# io-board-d-7.net
KiCad netlist of a schematic drawn in EAGLE
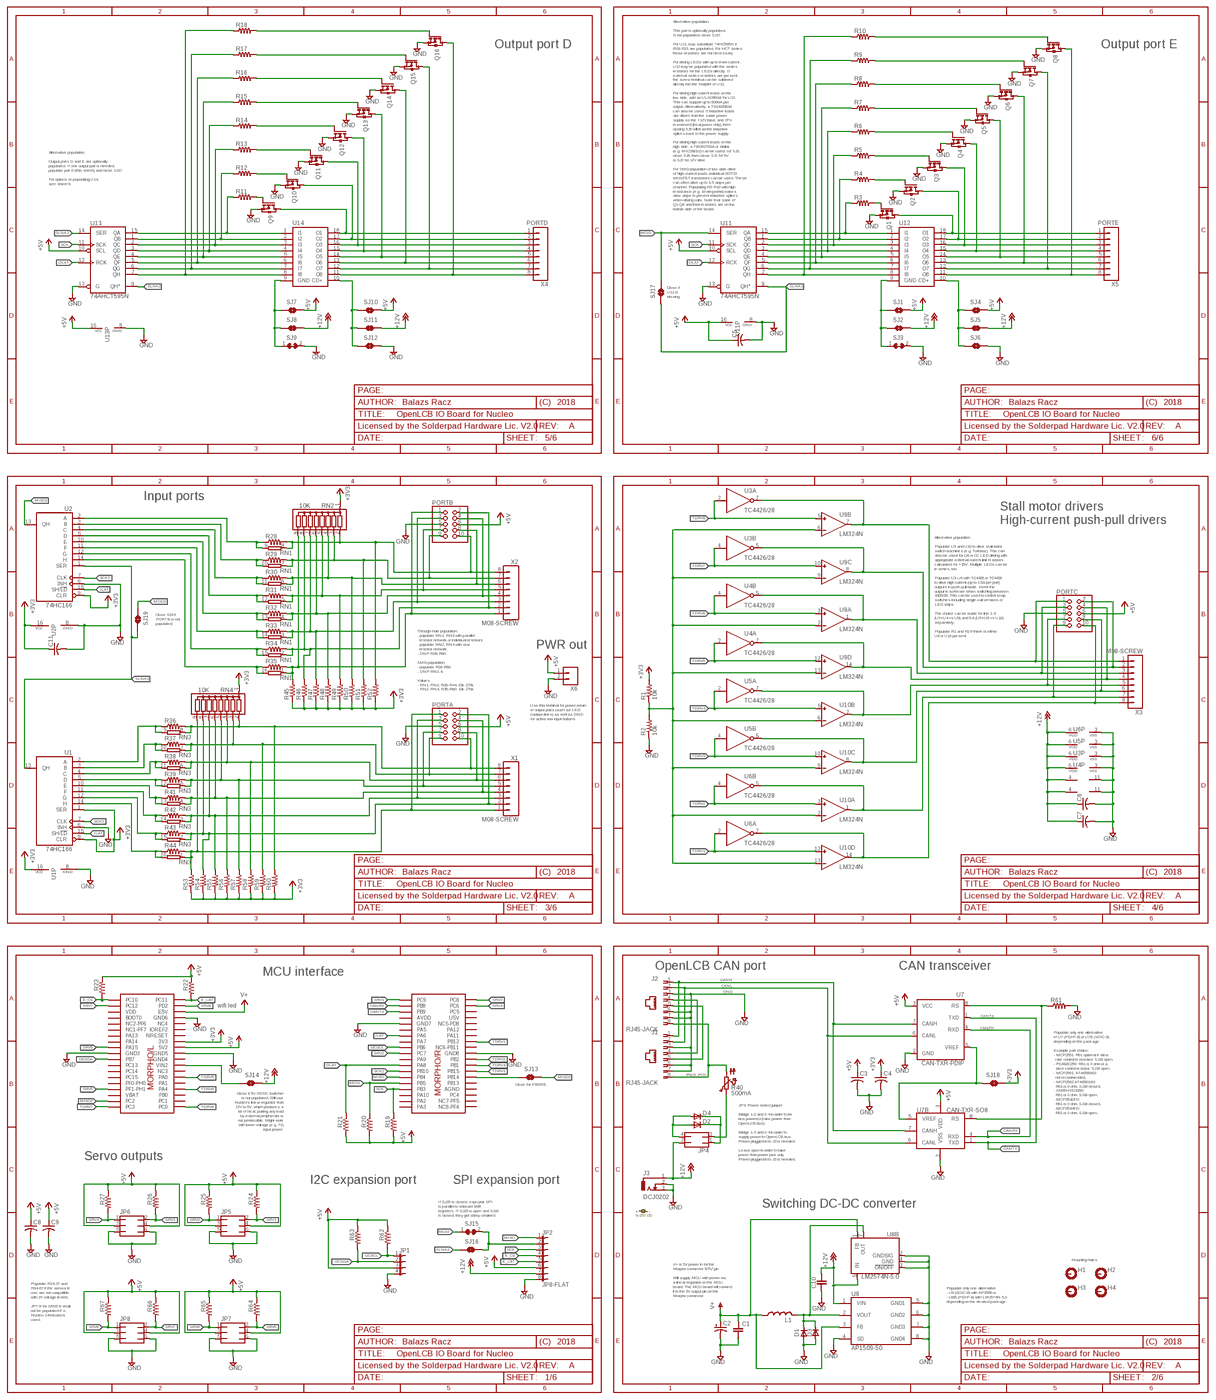
[diagram p0: schematic, sheet 1, overview]
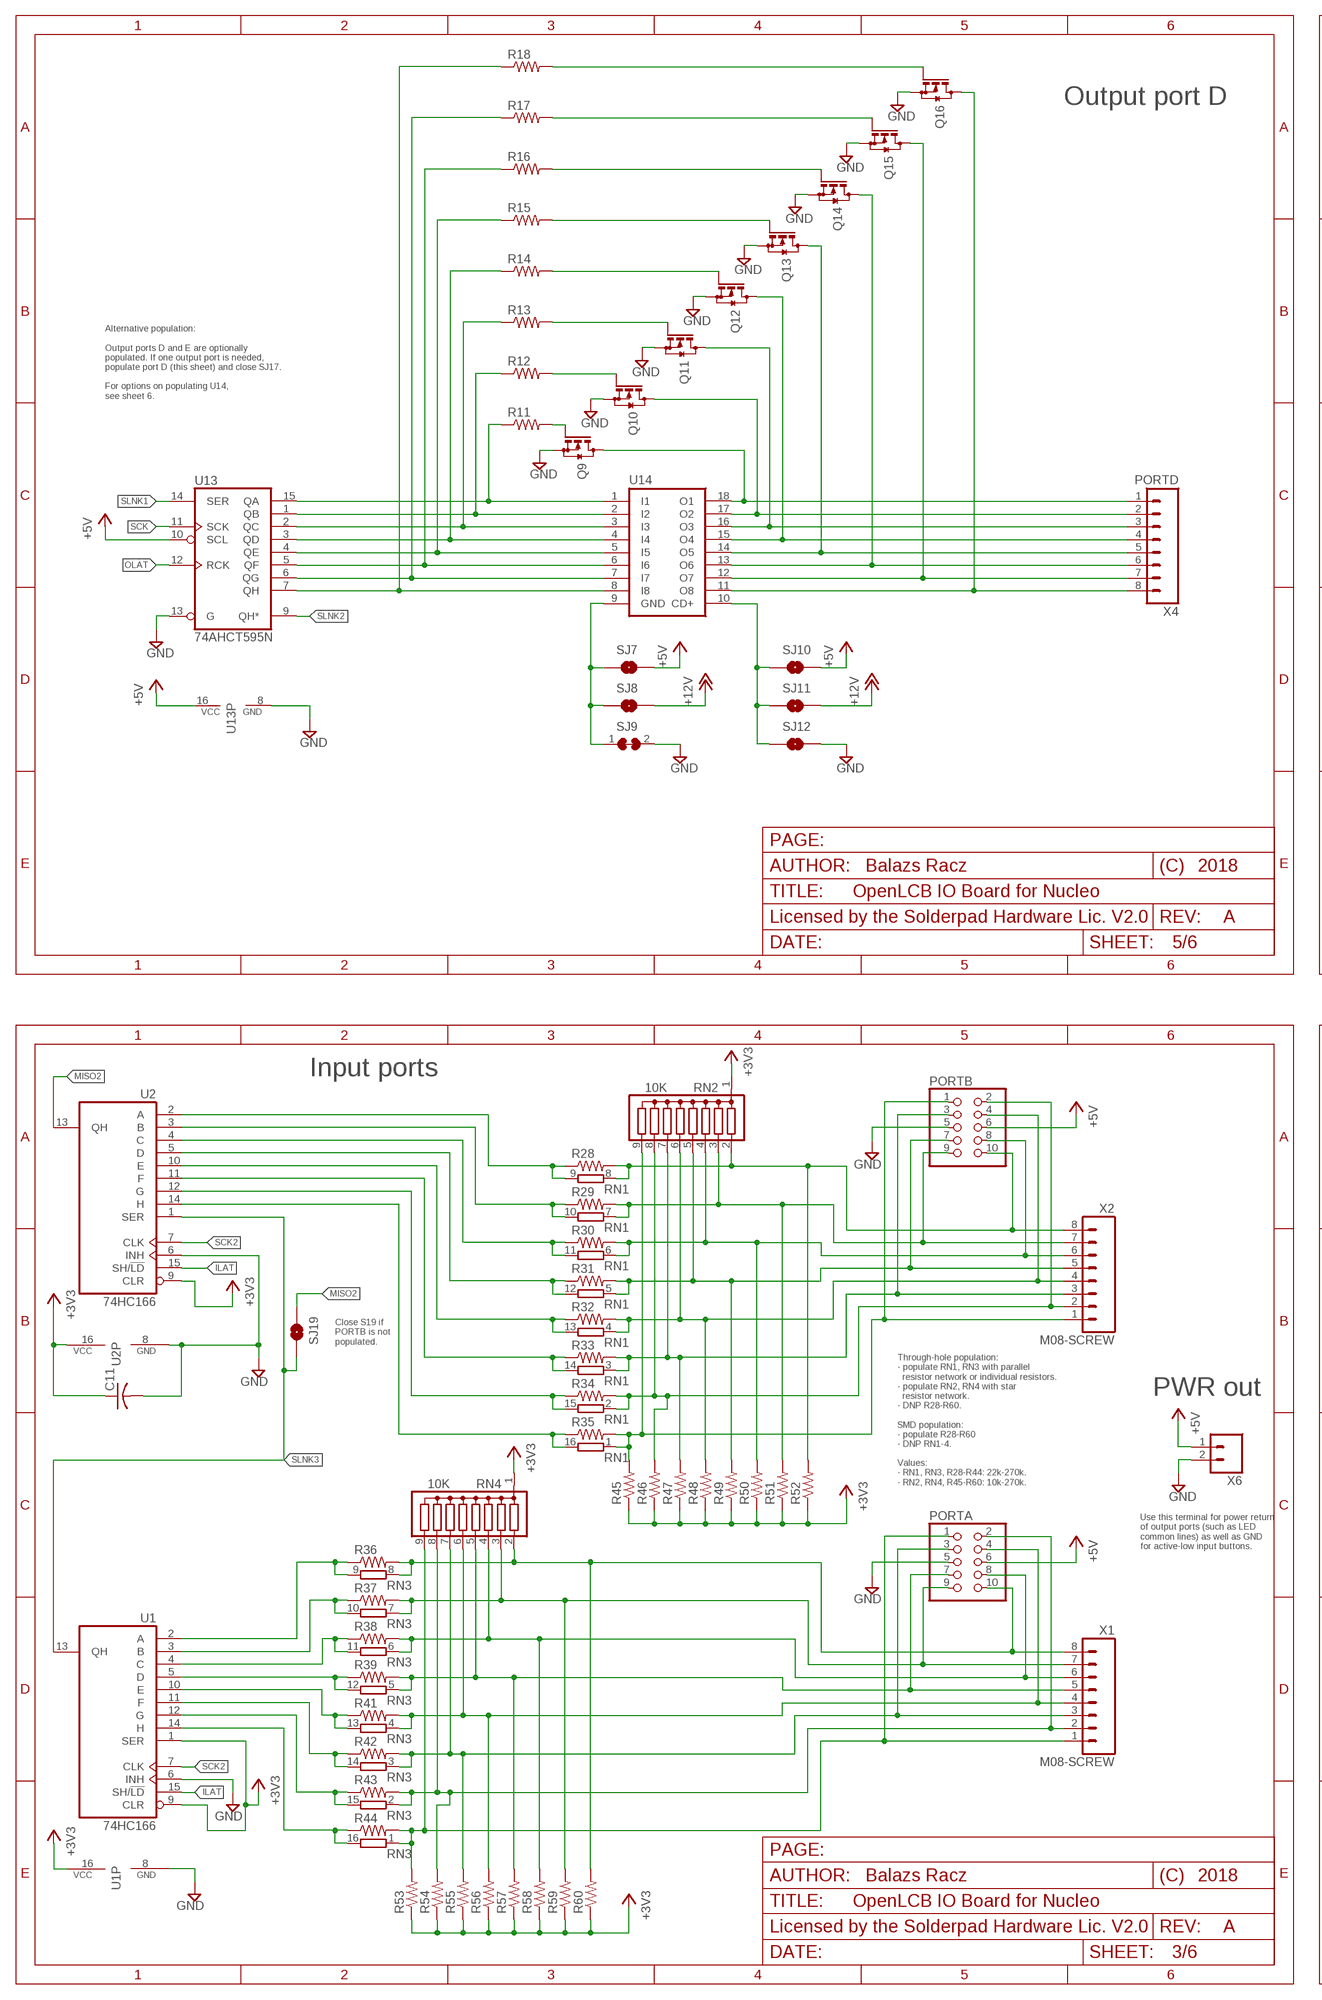
[diagram p1: schematic, sheet 1, part 1 of 4]
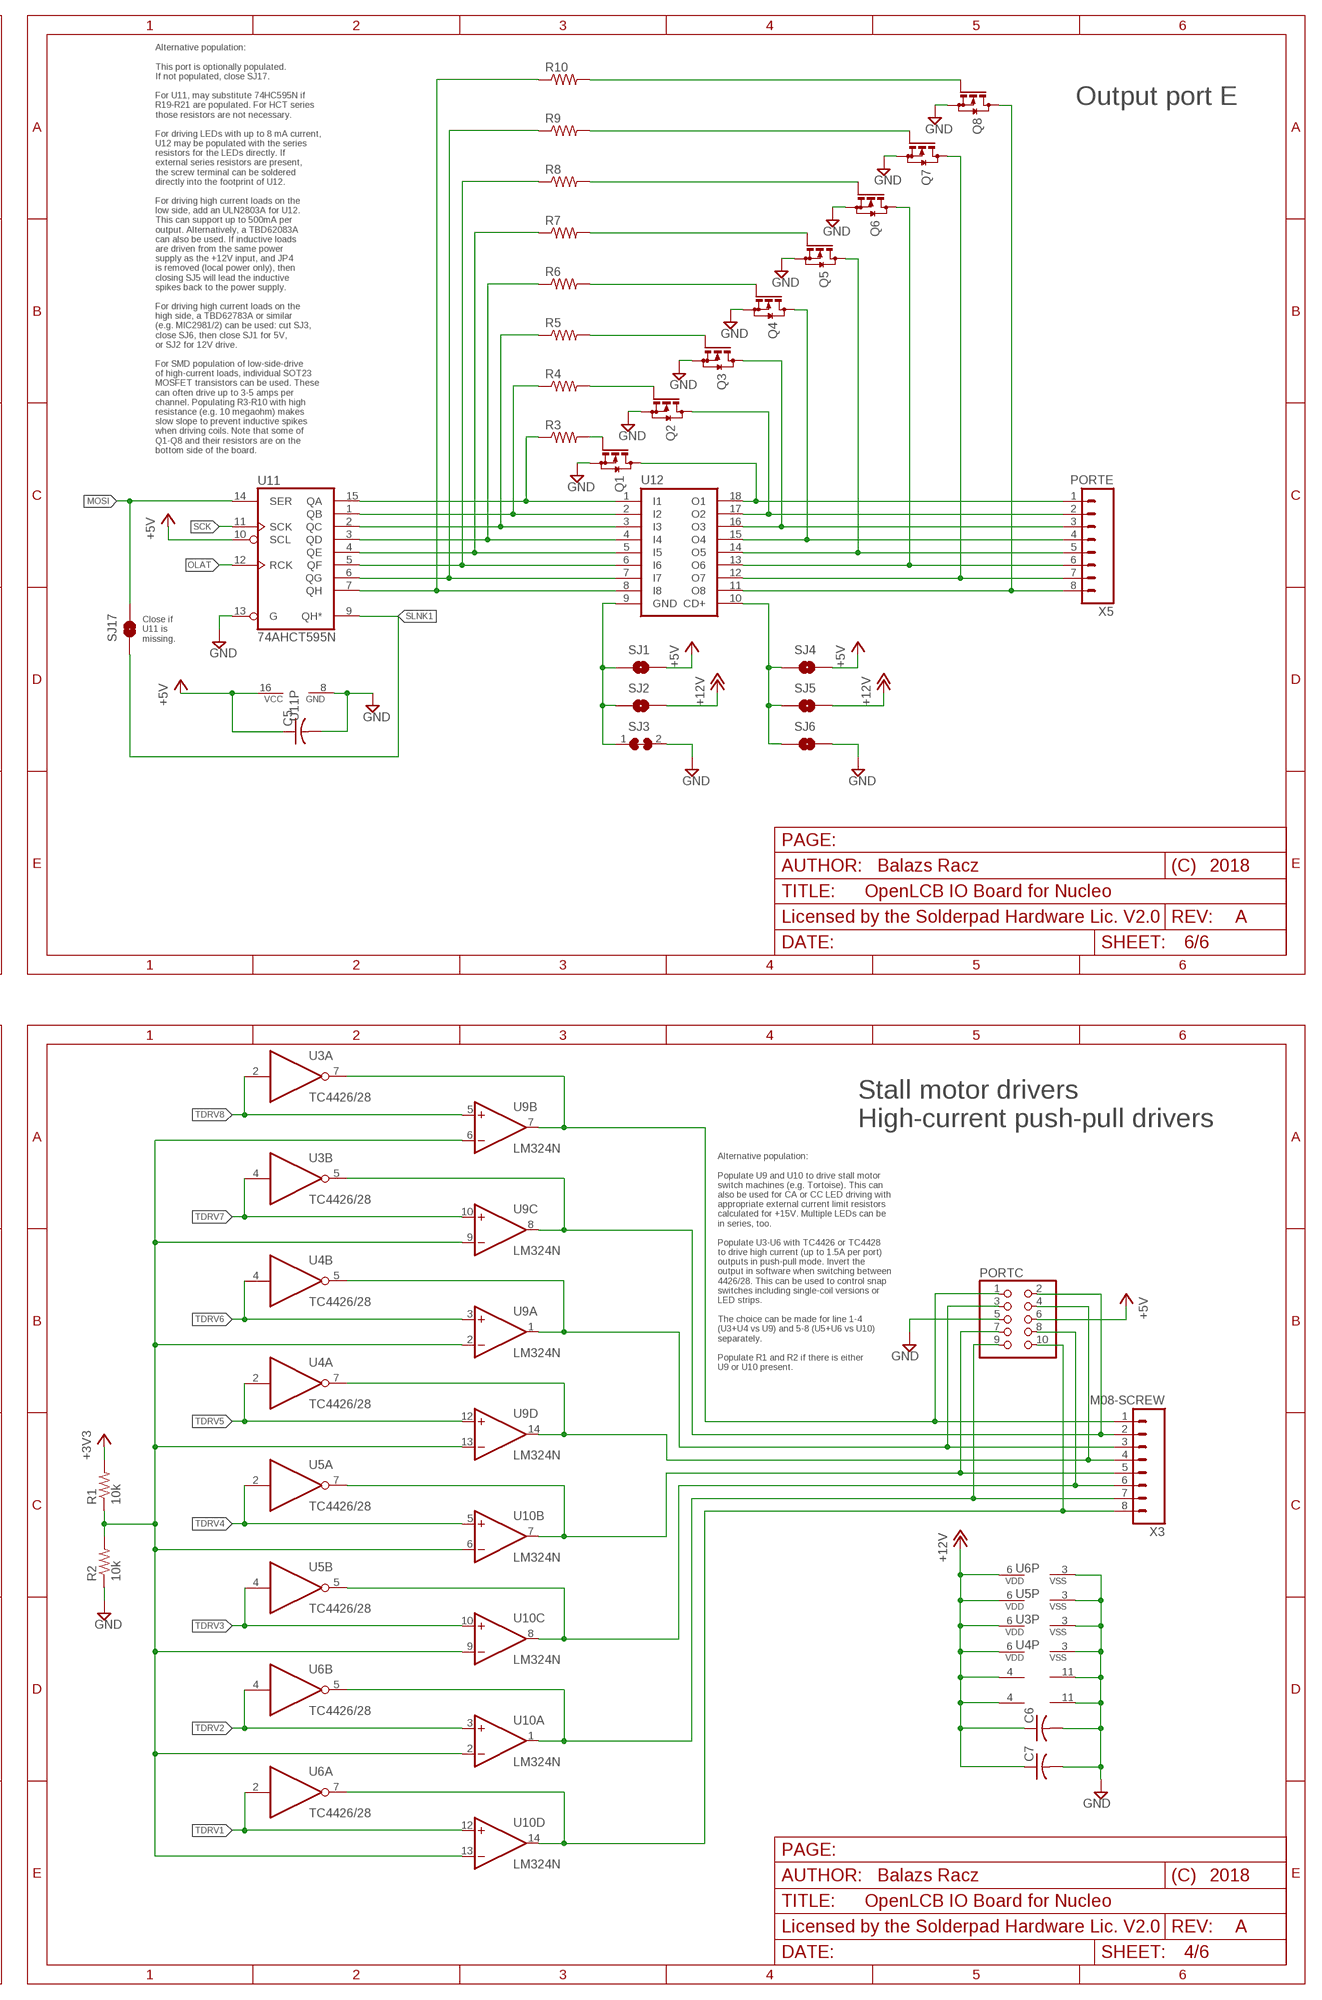
[diagram p2: schematic, sheet 1, part 2 of 4]
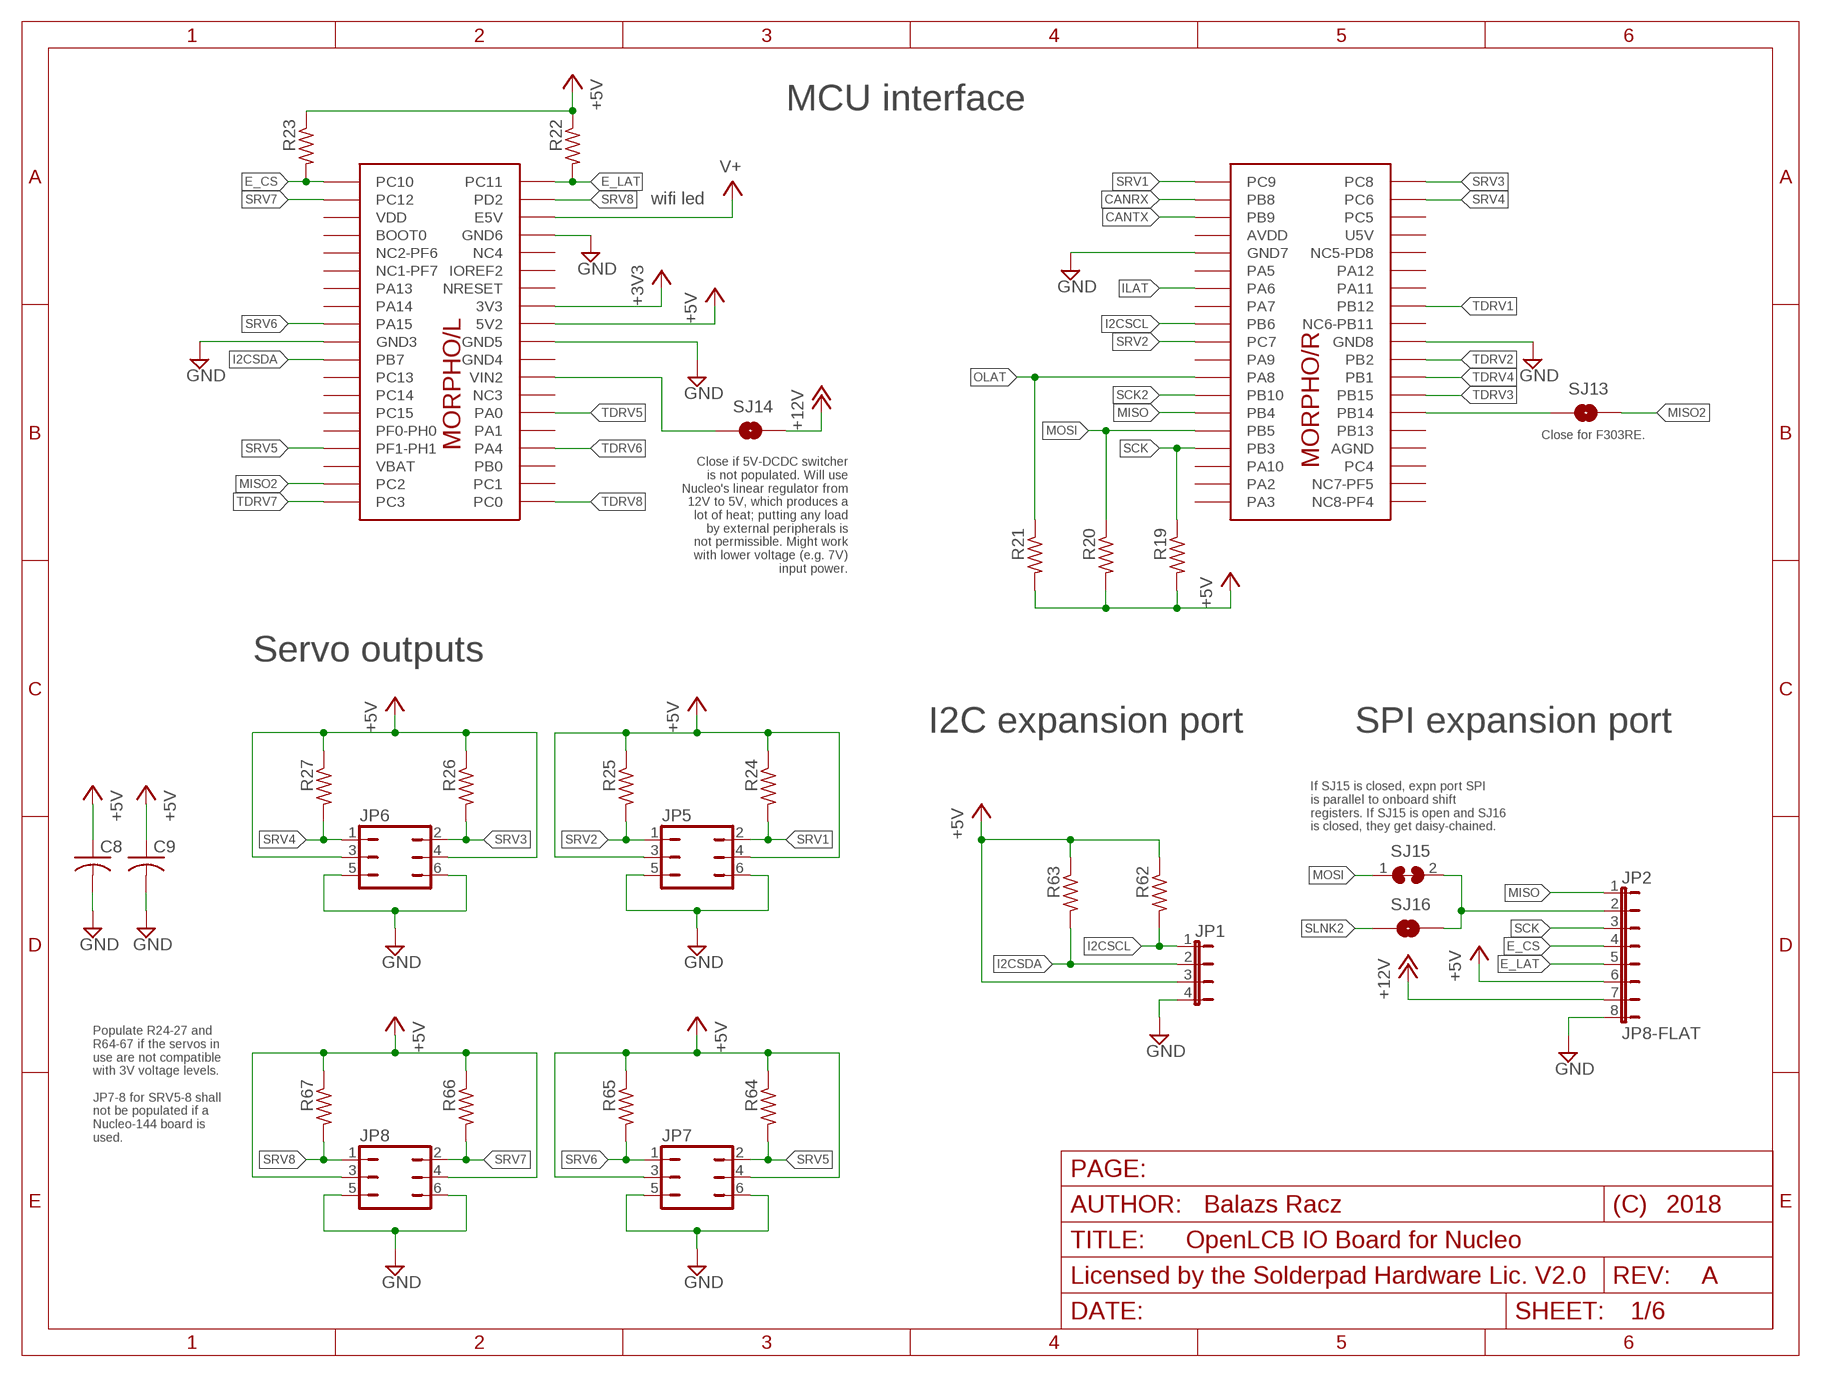
[diagram p3: schematic, sheet 1, part 3 of 4]
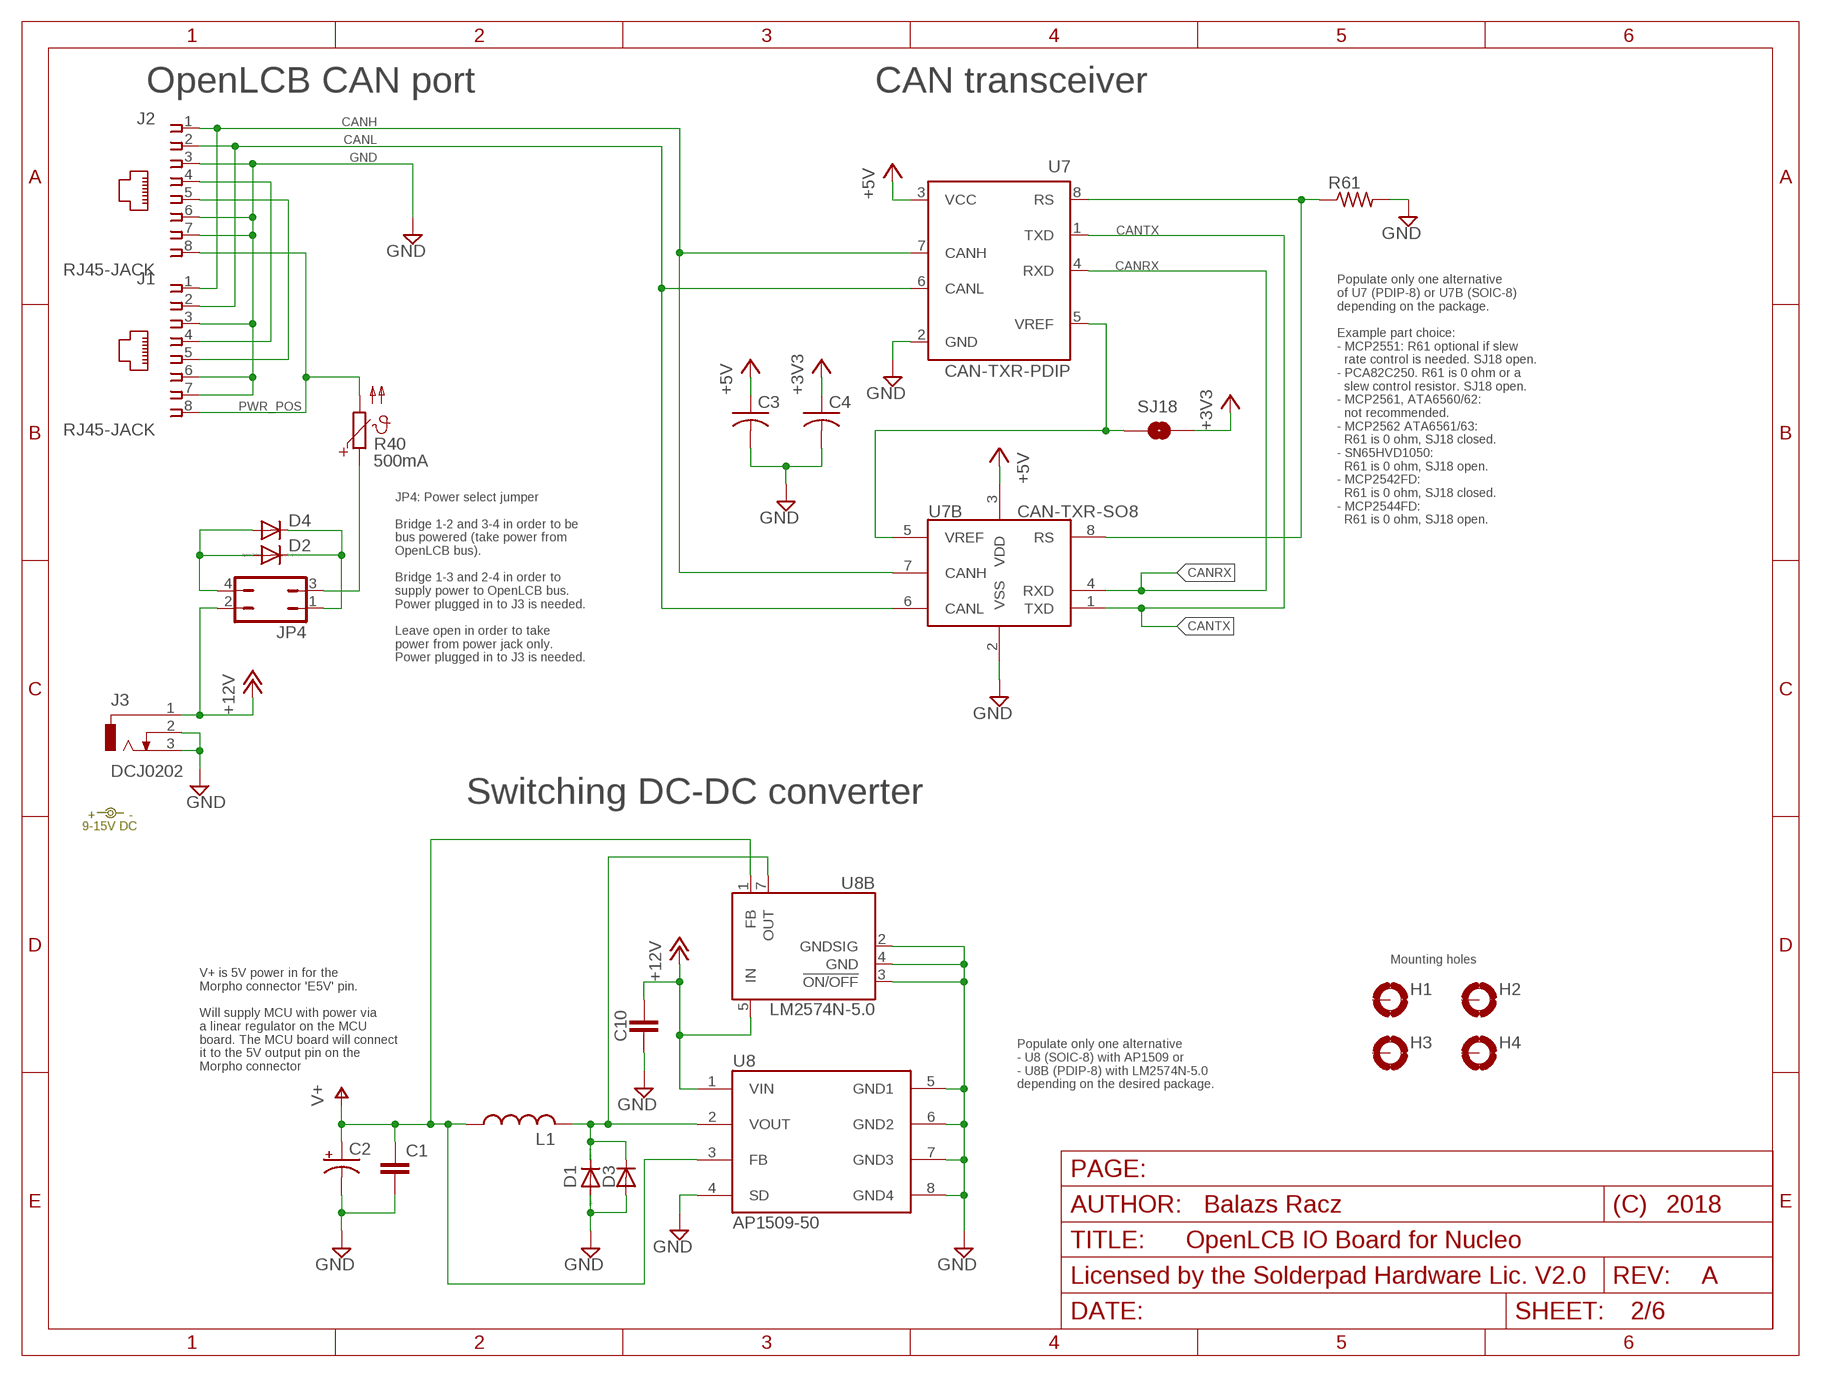
[diagram p4: schematic, sheet 1, part 4 of 4]

(export (version "E")
  (design (tool "Eeschema 10.0.6"))
  (components
    (comp (ref "+12V")
      (value "9-15V DC")
      (footprint "eagle-import:POWER_USAGE")
      (libsource (lib "eagle-import") (part "DOC-POWER_LABEL"))
    )
    (comp (ref "C1")
      (value "C-EUC1206")
      (footprint "eagle-import:C1206")
      (libsource (lib "eagle-import") (part "C-EUC1206"))
    )
    (comp (ref "C2")
      (value "CPOL-USE2.5-5")
      (footprint "eagle-import:E2,5-5")
      (libsource (lib "eagle-import") (part "CPOL-USE2.5-5"))
    )
    (comp (ref "C3")
      (value "C-USC0805")
      (footprint "eagle-import:C0805")
      (libsource (lib "eagle-import") (part "C-USC0805"))
    )
    (comp (ref "C4")
      (value "C-USC0805")
      (footprint "eagle-import:C0805")
      (libsource (lib "eagle-import") (part "C-USC0805"))
    )
    (comp (ref "C5")
      (value "C-USC0805")
      (footprint "eagle-import:C0805")
      (libsource (lib "eagle-import") (part "C-USC0805"))
    )
    (comp (ref "C6")
      (value "C-USC1206")
      (footprint "eagle-import:C1206")
      (libsource (lib "eagle-import") (part "C-USC1206"))
    )
    (comp (ref "C7")
      (value "C-USC1206")
      (footprint "eagle-import:C1206")
      (libsource (lib "eagle-import") (part "C-USC1206"))
    )
    (comp (ref "C8")
      (value "C-USC1206")
      (footprint "eagle-import:C1206")
      (libsource (lib "eagle-import") (part "C-USC1206"))
    )
    (comp (ref "C9")
      (value "C-USC1206")
      (footprint "eagle-import:C1206")
      (libsource (lib "eagle-import") (part "C-USC1206"))
    )
    (comp (ref "C10")
      (value "C-EUC1206")
      (footprint "eagle-import:C1206")
      (libsource (lib "eagle-import") (part "C-EUC1206"))
    )
    (comp (ref "C11")
      (value "C-USC0805")
      (footprint "eagle-import:C0805")
      (libsource (lib "eagle-import") (part "C-USC0805"))
    )
    (comp (ref "D1")
      (value "DIODE-DO41-7.6")
      (footprint "eagle-import:DO41-7.6")
      (libsource (lib "eagle-import") (part "DIODE-DO41-7.6"))
    )
    (comp (ref "D2")
      (value "DIODE-DO41-7.6")
      (footprint "eagle-import:DO41-7.6")
      (libsource (lib "eagle-import") (part "DIODE-DO41-7.6"))
    )
    (comp (ref "D3")
      (value "DIODEDO-214AA-NODOC")
      (footprint "eagle-import:DO214AA-NODOC")
      (libsource (lib "eagle-import") (part "DIODEDO-214AA-NODOC"))
    )
    (comp (ref "D4")
      (value "DIODEDO-214AA-NODOC")
      (footprint "eagle-import:DO214AA-NODOC")
      (libsource (lib "eagle-import") (part "DIODEDO-214AA-NODOC"))
    )
    (comp (ref "H1")
      (value "MOUNT-PAD-ROUND3.3")
      (footprint "eagle-import:3,3-PAD")
      (libsource (lib "eagle-import") (part "MOUNT-PAD-ROUND3.3"))
    )
    (comp (ref "H2")
      (value "MOUNT-PAD-ROUND3.3")
      (footprint "eagle-import:3,3-PAD")
      (libsource (lib "eagle-import") (part "MOUNT-PAD-ROUND3.3"))
    )
    (comp (ref "H3")
      (value "MOUNT-PAD-ROUND3.3")
      (footprint "eagle-import:3,3-PAD")
      (libsource (lib "eagle-import") (part "MOUNT-PAD-ROUND3.3"))
    )
    (comp (ref "H4")
      (value "MOUNT-PAD-ROUND3.3")
      (footprint "eagle-import:3,3-PAD")
      (libsource (lib "eagle-import") (part "MOUNT-PAD-ROUND3.3"))
    )
    (comp (ref "J1")
      (value "RJ45-JACK")
      (footprint "eagle-import:RJ45-PULSE-E5J88")
      (libsource (lib "eagle-import") (part "RJ45-JACKRJ45-PULSE-E5J00"))
    )
    (comp (ref "J2")
      (value "RJ45-JACK")
      (footprint "eagle-import:RJ45-PULSE-E5J88")
      (libsource (lib "eagle-import") (part "RJ45-JACKRJ45-PULSE-E5J00"))
    )
    (comp (ref "J3")
      (value "DCJ0202")
      (footprint "eagle-import:DCJ0202")
      (libsource (lib "eagle-import") (part "DCJ0202"))
    )
    (comp (ref "JP1")
      (value "JP4-FLAT")
      (footprint "eagle-import:JP4F")
      (libsource (lib "eagle-import") (part "JP4-FLAT"))
    )
    (comp (ref "JP2")
      (value "JP8-FLAT")
      (footprint "eagle-import:JP8F")
      (libsource (lib "eagle-import") (part "JP8-FLAT"))
    )
    (comp (ref "JP4")
      (value "JP2Q")
      (footprint "eagle-import:JP2Q")
      (libsource (lib "eagle-import") (part "JP2Q"))
    )
    (comp (ref "JP5")
      (value "JP3Q")
      (footprint "eagle-import:JP3Q")
      (libsource (lib "eagle-import") (part "JP3Q"))
    )
    (comp (ref "JP6")
      (value "JP3Q")
      (footprint "eagle-import:JP3Q")
      (libsource (lib "eagle-import") (part "JP3Q"))
    )
    (comp (ref "JP7")
      (value "JP3Q")
      (footprint "eagle-import:JP3Q")
      (libsource (lib "eagle-import") (part "JP3Q"))
    )
    (comp (ref "JP8")
      (value "JP3Q")
      (footprint "eagle-import:JP3Q")
      (libsource (lib "eagle-import") (part "JP3Q"))
    )
    (comp (ref "L1")
      (value "L-US")
      (footprint "eagle-import:L5-8,5")
      (libsource (lib "eagle-import") (part "L-US"))
    )
    (comp (ref "PORTA")
      (value "PINHD-2X5CN")
      (footprint "eagle-import:CON10M")
      (libsource (lib "eagle-import") (part "PINHD-2X5CN"))
    )
    (comp (ref "PORTB")
      (value "PINHD-2X5CN")
      (footprint "eagle-import:CON10M")
      (libsource (lib "eagle-import") (part "PINHD-2X5CN"))
    )
    (comp (ref "PORTC")
      (value "PINHD-2X5CN")
      (footprint "eagle-import:CON10M")
      (libsource (lib "eagle-import") (part "PINHD-2X5CN"))
    )
    (comp (ref "Q1")
      (value "BSS123")
      (footprint "eagle-import:SOT23")
      (libsource (lib "eagle-import") (part "BSS123"))
    )
    (comp (ref "Q2")
      (value "BSS123")
      (footprint "eagle-import:SOT23")
      (libsource (lib "eagle-import") (part "BSS123"))
    )
    (comp (ref "Q3")
      (value "BSS123")
      (footprint "eagle-import:SOT23")
      (libsource (lib "eagle-import") (part "BSS123"))
    )
    (comp (ref "Q4")
      (value "BSS123")
      (footprint "eagle-import:SOT23")
      (libsource (lib "eagle-import") (part "BSS123"))
    )
    (comp (ref "Q5")
      (value "BSS123")
      (footprint "eagle-import:SOT23")
      (libsource (lib "eagle-import") (part "BSS123"))
    )
    (comp (ref "Q6")
      (value "BSS123")
      (footprint "eagle-import:SOT23")
      (libsource (lib "eagle-import") (part "BSS123"))
    )
    (comp (ref "Q7")
      (value "BSS123")
      (footprint "eagle-import:SOT23")
      (libsource (lib "eagle-import") (part "BSS123"))
    )
    (comp (ref "Q8")
      (value "BSS123")
      (footprint "eagle-import:SOT23")
      (libsource (lib "eagle-import") (part "BSS123"))
    )
    (comp (ref "Q9")
      (value "BSS123")
      (footprint "eagle-import:SOT23")
      (libsource (lib "eagle-import") (part "BSS123"))
    )
    (comp (ref "Q10")
      (value "BSS123")
      (footprint "eagle-import:SOT23")
      (libsource (lib "eagle-import") (part "BSS123"))
    )
    (comp (ref "Q11")
      (value "BSS123")
      (footprint "eagle-import:SOT23")
      (libsource (lib "eagle-import") (part "BSS123"))
    )
    (comp (ref "Q12")
      (value "BSS123")
      (footprint "eagle-import:SOT23")
      (libsource (lib "eagle-import") (part "BSS123"))
    )
    (comp (ref "Q13")
      (value "BSS123")
      (footprint "eagle-import:SOT23")
      (libsource (lib "eagle-import") (part "BSS123"))
    )
    (comp (ref "Q14")
      (value "BSS123")
      (footprint "eagle-import:SOT23")
      (libsource (lib "eagle-import") (part "BSS123"))
    )
    (comp (ref "Q15")
      (value "BSS123")
      (footprint "eagle-import:SOT23")
      (libsource (lib "eagle-import") (part "BSS123"))
    )
    (comp (ref "Q16")
      (value "BSS123")
      (footprint "eagle-import:SOT23")
      (libsource (lib "eagle-import") (part "BSS123"))
    )
    (comp (ref "R1")
      (value "10k")
      (footprint "eagle-import:R0805")
      (libsource (lib "eagle-import") (part "R-US_R0805"))
    )
    (comp (ref "R2")
      (value "10k")
      (footprint "eagle-import:R0805")
      (libsource (lib "eagle-import") (part "R-US_R0805"))
    )
    (comp (ref "R3")
      (value "R-US_R0603")
      (footprint "eagle-import:R0603")
      (libsource (lib "eagle-import") (part "R-US_R0603"))
    )
    (comp (ref "R4")
      (value "R-US_R0603")
      (footprint "eagle-import:R0603")
      (libsource (lib "eagle-import") (part "R-US_R0603"))
    )
    (comp (ref "R5")
      (value "R-US_R0603")
      (footprint "eagle-import:R0603")
      (libsource (lib "eagle-import") (part "R-US_R0603"))
    )
    (comp (ref "R6")
      (value "R-US_R0603")
      (footprint "eagle-import:R0603")
      (libsource (lib "eagle-import") (part "R-US_R0603"))
    )
    (comp (ref "R7")
      (value "R-US_R0603")
      (footprint "eagle-import:R0603")
      (libsource (lib "eagle-import") (part "R-US_R0603"))
    )
    (comp (ref "R8")
      (value "R-US_R0603")
      (footprint "eagle-import:R0603")
      (libsource (lib "eagle-import") (part "R-US_R0603"))
    )
    (comp (ref "R9")
      (value "R-US_R0603")
      (footprint "eagle-import:R0603")
      (libsource (lib "eagle-import") (part "R-US_R0603"))
    )
    (comp (ref "R10")
      (value "R-US_R0603")
      (footprint "eagle-import:R0603")
      (libsource (lib "eagle-import") (part "R-US_R0603"))
    )
    (comp (ref "R11")
      (value "R-US_R0603")
      (footprint "eagle-import:R0603")
      (libsource (lib "eagle-import") (part "R-US_R0603"))
    )
    (comp (ref "R12")
      (value "R-US_R0603")
      (footprint "eagle-import:R0603")
      (libsource (lib "eagle-import") (part "R-US_R0603"))
    )
    (comp (ref "R13")
      (value "R-US_R0603")
      (footprint "eagle-import:R0603")
      (libsource (lib "eagle-import") (part "R-US_R0603"))
    )
    (comp (ref "R14")
      (value "R-US_R0603")
      (footprint "eagle-import:R0603")
      (libsource (lib "eagle-import") (part "R-US_R0603"))
    )
    (comp (ref "R15")
      (value "R-US_R0603")
      (footprint "eagle-import:R0603")
      (libsource (lib "eagle-import") (part "R-US_R0603"))
    )
    (comp (ref "R16")
      (value "R-US_R0603")
      (footprint "eagle-import:R0603")
      (libsource (lib "eagle-import") (part "R-US_R0603"))
    )
    (comp (ref "R17")
      (value "R-US_R0603")
      (footprint "eagle-import:R0603")
      (libsource (lib "eagle-import") (part "R-US_R0603"))
    )
    (comp (ref "R18")
      (value "R-US_R0603")
      (footprint "eagle-import:R0603")
      (libsource (lib "eagle-import") (part "R-US_R0603"))
    )
    (comp (ref "R19")
      (value "R-US_R0805")
      (footprint "eagle-import:R0805")
      (libsource (lib "eagle-import") (part "rcl_334_R-US_R0805"))
    )
    (comp (ref "R20")
      (value "R-US_R0805")
      (footprint "eagle-import:R0805")
      (libsource (lib "eagle-import") (part "rcl_334_R-US_R0805"))
    )
    (comp (ref "R21")
      (value "R-US_R0805")
      (footprint "eagle-import:R0805")
      (libsource (lib "eagle-import") (part "rcl_334_R-US_R0805"))
    )
    (comp (ref "R22")
      (value "R-US_R0805")
      (footprint "eagle-import:R0805")
      (libsource (lib "eagle-import") (part "rcl_334_R-US_R0805"))
    )
    (comp (ref "R23")
      (value "R-US_R0805")
      (footprint "eagle-import:R0805")
      (libsource (lib "eagle-import") (part "rcl_334_R-US_R0805"))
    )
    (comp (ref "R24")
      (value "R-US_R0805")
      (footprint "eagle-import:R0805")
      (libsource (lib "eagle-import") (part "rcl_334_R-US_R0805"))
    )
    (comp (ref "R25")
      (value "R-US_R0805")
      (footprint "eagle-import:R0805")
      (libsource (lib "eagle-import") (part "rcl_334_R-US_R0805"))
    )
    (comp (ref "R26")
      (value "R-US_R0805")
      (footprint "eagle-import:R0805")
      (libsource (lib "eagle-import") (part "rcl_334_R-US_R0805"))
    )
    (comp (ref "R27")
      (value "R-US_R0805")
      (footprint "eagle-import:R0805")
      (libsource (lib "eagle-import") (part "rcl_334_R-US_R0805"))
    )
    (comp (ref "R28")
      (value "R-US_R0603")
      (footprint "eagle-import:R0603")
      (libsource (lib "eagle-import") (part "rcl_334_R-US_R0603"))
    )
    (comp (ref "R29")
      (value "R-US_R0603")
      (footprint "eagle-import:R0603")
      (libsource (lib "eagle-import") (part "rcl_334_R-US_R0603"))
    )
    (comp (ref "R30")
      (value "R-US_R0603")
      (footprint "eagle-import:R0603")
      (libsource (lib "eagle-import") (part "rcl_334_R-US_R0603"))
    )
    (comp (ref "R31")
      (value "R-US_R0603")
      (footprint "eagle-import:R0603")
      (libsource (lib "eagle-import") (part "rcl_334_R-US_R0603"))
    )
    (comp (ref "R32")
      (value "R-US_R0603")
      (footprint "eagle-import:R0603")
      (libsource (lib "eagle-import") (part "rcl_334_R-US_R0603"))
    )
    (comp (ref "R33")
      (value "R-US_R0603")
      (footprint "eagle-import:R0603")
      (libsource (lib "eagle-import") (part "rcl_334_R-US_R0603"))
    )
    (comp (ref "R34")
      (value "R-US_R0603")
      (footprint "eagle-import:R0603")
      (libsource (lib "eagle-import") (part "rcl_334_R-US_R0603"))
    )
    (comp (ref "R35")
      (value "R-US_R0603")
      (footprint "eagle-import:R0603")
      (libsource (lib "eagle-import") (part "rcl_334_R-US_R0603"))
    )
    (comp (ref "R36")
      (value "R-US_R0603")
      (footprint "eagle-import:R0603")
      (libsource (lib "eagle-import") (part "rcl_334_R-US_R0603"))
    )
    (comp (ref "R37")
      (value "R-US_R0603")
      (footprint "eagle-import:R0603")
      (libsource (lib "eagle-import") (part "rcl_334_R-US_R0603"))
    )
    (comp (ref "R38")
      (value "R-US_R0603")
      (footprint "eagle-import:R0603")
      (libsource (lib "eagle-import") (part "rcl_334_R-US_R0603"))
    )
    (comp (ref "R39")
      (value "R-US_R0603")
      (footprint "eagle-import:R0603")
      (libsource (lib "eagle-import") (part "rcl_334_R-US_R0603"))
    )
    (comp (ref "R40")
      (value "500mA")
      (footprint "eagle-import:PTC1812")
      (libsource (lib "eagle-import") (part "PTC_1812"))
    )
    (comp (ref "R41")
      (value "R-US_R0603")
      (footprint "eagle-import:R0603")
      (libsource (lib "eagle-import") (part "rcl_334_R-US_R0603"))
    )
    (comp (ref "R42")
      (value "R-US_R0603")
      (footprint "eagle-import:R0603")
      (libsource (lib "eagle-import") (part "rcl_334_R-US_R0603"))
    )
    (comp (ref "R43")
      (value "R-US_R0603")
      (footprint "eagle-import:R0603")
      (libsource (lib "eagle-import") (part "rcl_334_R-US_R0603"))
    )
    (comp (ref "R44")
      (value "R-US_R0603")
      (footprint "eagle-import:R0603")
      (libsource (lib "eagle-import") (part "rcl_334_R-US_R0603"))
    )
    (comp (ref "R45")
      (value "R-US")
      (footprint "eagle-import:R0603")
      (libsource (lib "eagle-import") (part "R-US"))
    )
    (comp (ref "R46")
      (value "R-US")
      (footprint "eagle-import:R0603")
      (libsource (lib "eagle-import") (part "R-US"))
    )
    (comp (ref "R47")
      (value "R-US")
      (footprint "eagle-import:R0603")
      (libsource (lib "eagle-import") (part "R-US"))
    )
    (comp (ref "R48")
      (value "R-US")
      (footprint "eagle-import:R0603")
      (libsource (lib "eagle-import") (part "R-US"))
    )
    (comp (ref "R49")
      (value "R-US")
      (footprint "eagle-import:R0603")
      (libsource (lib "eagle-import") (part "R-US"))
    )
    (comp (ref "R50")
      (value "R-US")
      (footprint "eagle-import:R0603")
      (libsource (lib "eagle-import") (part "R-US"))
    )
    (comp (ref "R51")
      (value "R-US")
      (footprint "eagle-import:R0603")
      (libsource (lib "eagle-import") (part "R-US"))
    )
    (comp (ref "R52")
      (value "R-US")
      (footprint "eagle-import:R0603")
      (libsource (lib "eagle-import") (part "R-US"))
    )
    (comp (ref "R53")
      (value "R-US")
      (footprint "eagle-import:R0603")
      (libsource (lib "eagle-import") (part "R-US"))
    )
    (comp (ref "R54")
      (value "R-US")
      (footprint "eagle-import:R0603")
      (libsource (lib "eagle-import") (part "R-US"))
    )
    (comp (ref "R55")
      (value "R-US")
      (footprint "eagle-import:R0603")
      (libsource (lib "eagle-import") (part "R-US"))
    )
    (comp (ref "R56")
      (value "R-US")
      (footprint "eagle-import:R0603")
      (libsource (lib "eagle-import") (part "R-US"))
    )
    (comp (ref "R57")
      (value "R-US")
      (footprint "eagle-import:R0603")
      (libsource (lib "eagle-import") (part "R-US"))
    )
    (comp (ref "R58")
      (value "R-US")
      (footprint "eagle-import:R0603")
      (libsource (lib "eagle-import") (part "R-US"))
    )
    (comp (ref "R59")
      (value "R-US")
      (footprint "eagle-import:R0603")
      (libsource (lib "eagle-import") (part "R-US"))
    )
    (comp (ref "R60")
      (value "R-US")
      (footprint "eagle-import:R0603")
      (libsource (lib "eagle-import") (part "R-US"))
    )
    (comp (ref "R61")
      (value "R-US_R0805")
      (footprint "eagle-import:R0805")
      (libsource (lib "eagle-import") (part "rcl_334_R-US_R0805"))
    )
    (comp (ref "R62")
      (value "R-US_R0805")
      (footprint "eagle-import:R0805")
      (libsource (lib "eagle-import") (part "rcl_334_R-US_R0805"))
    )
    (comp (ref "R63")
      (value "R-US_R0805")
      (footprint "eagle-import:R0805")
      (libsource (lib "eagle-import") (part "rcl_334_R-US_R0805"))
    )
    (comp (ref "R64")
      (value "R-US_R0805")
      (footprint "eagle-import:R0805")
      (libsource (lib "eagle-import") (part "rcl_334_R-US_R0805"))
    )
    (comp (ref "R65")
      (value "R-US_R0805")
      (footprint "eagle-import:R0805")
      (libsource (lib "eagle-import") (part "rcl_334_R-US_R0805"))
    )
    (comp (ref "R66")
      (value "R-US_R0805")
      (footprint "eagle-import:R0805")
      (libsource (lib "eagle-import") (part "rcl_334_R-US_R0805"))
    )
    (comp (ref "R67")
      (value "R-US_R0805")
      (footprint "eagle-import:R0805")
      (libsource (lib "eagle-import") (part "rcl_334_R-US_R0805"))
    )
    (comp (ref "RN1")
      (value "8R-P")
      (footprint "eagle-import:DIL16")
      (libsource (lib "eagle-import") (part "8R-P"))
    )
    (comp (ref "RN2")
      (value "10K")
      (footprint "eagle-import:SIL9")
      (libsource (lib "eagle-import") (part "G08R"))
    )
    (comp (ref "RN3")
      (value "8R-P")
      (footprint "eagle-import:DIL16")
      (libsource (lib "eagle-import") (part "8R-P"))
    )
    (comp (ref "RN4")
      (value "10K")
      (footprint "eagle-import:SIL9")
      (libsource (lib "eagle-import") (part "G08R"))
    )
    (comp (ref "SJ1")
      (value "SJRND2")
      (footprint "eagle-import:SJ_RND2")
      (libsource (lib "eagle-import") (part "SJRND2"))
    )
    (comp (ref "SJ2")
      (value "SJRND2")
      (footprint "eagle-import:SJ_RND2")
      (libsource (lib "eagle-import") (part "SJRND2"))
    )
    (comp (ref "SJ3")
      (value "SJ-C")
      (footprint "eagle-import:SJW-C")
      (libsource (lib "eagle-import") (part "SJ-C"))
    )
    (comp (ref "SJ4")
      (value "SJRND2")
      (footprint "eagle-import:SJ_RND2")
      (libsource (lib "eagle-import") (part "SJRND2"))
    )
    (comp (ref "SJ5")
      (value "SJRND2")
      (footprint "eagle-import:SJ_RND2")
      (libsource (lib "eagle-import") (part "SJRND2"))
    )
    (comp (ref "SJ6")
      (value "SJRND2")
      (footprint "eagle-import:SJ_RND2")
      (libsource (lib "eagle-import") (part "SJRND2"))
    )
    (comp (ref "SJ7")
      (value "SJRND2")
      (footprint "eagle-import:SJ_RND2")
      (libsource (lib "eagle-import") (part "SJRND2"))
    )
    (comp (ref "SJ8")
      (value "SJRND2")
      (footprint "eagle-import:SJ_RND2")
      (libsource (lib "eagle-import") (part "SJRND2"))
    )
    (comp (ref "SJ9")
      (value "SJ-C")
      (footprint "eagle-import:SJW-C")
      (libsource (lib "eagle-import") (part "SJ-C"))
    )
    (comp (ref "SJ10")
      (value "SJRND2")
      (footprint "eagle-import:SJ_RND2")
      (libsource (lib "eagle-import") (part "SJRND2"))
    )
    (comp (ref "SJ11")
      (value "SJRND2")
      (footprint "eagle-import:SJ_RND2")
      (libsource (lib "eagle-import") (part "SJRND2"))
    )
    (comp (ref "SJ12")
      (value "SJRND2")
      (footprint "eagle-import:SJ_RND2")
      (libsource (lib "eagle-import") (part "SJRND2"))
    )
    (comp (ref "SJ13")
      (value "SJRND2")
      (footprint "eagle-import:SJ_RND2")
      (libsource (lib "eagle-import") (part "SJRND2"))
    )
    (comp (ref "SJ14")
      (value "SJRND2")
      (footprint "eagle-import:SJ_RND2")
      (libsource (lib "eagle-import") (part "SJRND2"))
    )
    (comp (ref "SJ15")
      (value "SJ-C")
      (footprint "eagle-import:SJW-C")
      (libsource (lib "eagle-import") (part "SJ-C"))
    )
    (comp (ref "SJ16")
      (value "SJRND2")
      (footprint "eagle-import:SJ_RND2")
      (libsource (lib "eagle-import") (part "SJRND2"))
    )
    (comp (ref "SJ17")
      (value "SJRND2")
      (footprint "eagle-import:SJ_RND2")
      (libsource (lib "eagle-import") (part "SJRND2"))
    )
    (comp (ref "SJ18")
      (value "SJRND2")
      (footprint "eagle-import:SJ_RND2")
      (libsource (lib "eagle-import") (part "SJRND2"))
    )
    (comp (ref "SJ19")
      (value "SJRND2")
      (footprint "eagle-import:SJ_RND2")
      (libsource (lib "eagle-import") (part "SJRND2"))
    )
    (comp (ref "U$1")
      (value "NUCLEO_64_GENERIC")
      (footprint "eagle-import:NUCLEO_BRD_BASE64")
      (libsource (lib "eagle-import") (part "NUCLEO_64_GENERIC"))
    )
    (comp (ref "U1")
      (value "74HC166")
      (footprint "eagle-import:DIL16")
      (libsource (lib "eagle-import") (part "74166N"))
    )
    (comp (ref "U2")
      (value "74HC166")
      (footprint "eagle-import:DIL16")
      (libsource (lib "eagle-import") (part "74166N"))
    )
    (comp (ref "U3")
      (value "TC4426/28")
      (footprint "eagle-import:DIL08-LONG")
      (libsource (lib "eagle-import") (part "TC4426APDIP"))
    )
    (comp (ref "U4")
      (value "TC4426/28")
      (footprint "eagle-import:DIL08-LONG")
      (libsource (lib "eagle-import") (part "TC4426APDIP"))
    )
    (comp (ref "U5")
      (value "TC4426/28")
      (footprint "eagle-import:DIL08-LONG")
      (libsource (lib "eagle-import") (part "TC4426APDIP"))
    )
    (comp (ref "U6")
      (value "TC4426/28")
      (footprint "eagle-import:DIL08-LONG")
      (libsource (lib "eagle-import") (part "TC4426APDIP"))
    )
    (comp (ref "U7")
      (value "CAN-TXR-PDIP")
      (footprint "eagle-import:DIL08")
      (libsource (lib "eagle-import") (part "PCA82C250"))
    )
    (comp (ref "U7B")
      (value "CAN-TXR-SO8")
      (footprint "eagle-import:SO-08")
      (libsource (lib "eagle-import") (part "MCP2551-SN"))
    )
    (comp (ref "U8")
      (value "AP1509-50")
      (footprint "eagle-import:SO-08")
      (libsource (lib "eagle-import") (part "AP1509"))
    )
    (comp (ref "U8B")
      (value "LM2574N-5.0")
      (footprint "eagle-import:DIL08")
      (libsource (lib "eagle-import") (part "LM2574?-N5.0"))
    )
    (comp (ref "U9")
      (value "LM324N")
      (footprint "eagle-import:DIL14")
      (libsource (lib "eagle-import") (part "LM324N"))
    )
    (comp (ref "U10")
      (value "LM324N")
      (footprint "eagle-import:DIL14")
      (libsource (lib "eagle-import") (part "LM324N"))
    )
    (comp (ref "U11")
      (value "74AHCT595N")
      (footprint "eagle-import:DIL16")
      (libsource (lib "eagle-import") (part "74595NHCT"))
    )
    (comp (ref "U12")
      (value "ULN2803A")
      (footprint "eagle-import:DIL18-THIN")
      (libsource (lib "eagle-import") (part "ULN2803A"))
    )
    (comp (ref "U13")
      (value "74AHCT595N")
      (footprint "eagle-import:DIL16")
      (libsource (lib "eagle-import") (part "74595NHCT"))
    )
    (comp (ref "U14")
      (value "ULN2803A")
      (footprint "eagle-import:DIL18-THIN")
      (libsource (lib "eagle-import") (part "ULN2803A"))
    )
    (comp (ref "X1")
      (value "M08-SCREW")
      (footprint "eagle-import:1X08_TERMINAL")
      (libsource (lib "eagle-import") (part "M08-SCREW"))
    )
    (comp (ref "X2")
      (value "M08-SCREW")
      (footprint "eagle-import:1X08_TERMINAL")
      (libsource (lib "eagle-import") (part "M08-SCREW"))
    )
    (comp (ref "X3")
      (value "M08-SCREW")
      (footprint "eagle-import:1X08_TERMINAL")
      (libsource (lib "eagle-import") (part "M08-SCREW"))
    )
    (comp (ref "X4")
      (value "PORTD")
      (footprint "eagle-import:1X08_TERMINAL")
      (libsource (lib "eagle-import") (part "M08-SCREW"))
    )
    (comp (ref "X5")
      (value "PORTE")
      (footprint "eagle-import:1X08_TERMINAL")
      (libsource (lib "eagle-import") (part "M08-SCREW"))
    )
    (comp (ref "X6")
      (value "CONNECTOR-M023.5MM-LOCK")
      (footprint "eagle-import:SCREWTERMINAL-3.5MM-2_LOCK")
      (libsource (lib "eagle-import") (part "CONNECTOR-M023.5MM-LOCK"))
    )
  )
  (nets
    (net (code "1") (name "+3V3") (class "Default")
      (node (ref "C11") (pin "1") (pinfunction "1_1") (pintype "passive"))
      (node (ref "C4") (pin "1") (pinfunction "1_1") (pintype "passive"))
      (node (ref "R1") (pin "2") (pinfunction "2_2") (pintype "passive"))
      (node (ref "R45") (pin "1") (pinfunction "1_1") (pintype "passive"))
      (node (ref "R46") (pin "1") (pinfunction "1_1") (pintype "passive"))
      (node (ref "R47") (pin "1") (pinfunction "1_1") (pintype "passive"))
      (node (ref "R48") (pin "1") (pinfunction "1_1") (pintype "passive"))
      (node (ref "R49") (pin "1") (pinfunction "1_1") (pintype "passive"))
      (node (ref "R50") (pin "1") (pinfunction "1_1") (pintype "passive"))
      (node (ref "R51") (pin "1") (pinfunction "1_1") (pintype "passive"))
      (node (ref "R52") (pin "1") (pinfunction "1_1") (pintype "passive"))
      (node (ref "R53") (pin "1") (pinfunction "1_1") (pintype "passive"))
      (node (ref "R54") (pin "1") (pinfunction "1_1") (pintype "passive"))
      (node (ref "R55") (pin "1") (pinfunction "1_1") (pintype "passive"))
      (node (ref "R56") (pin "1") (pinfunction "1_1") (pintype "passive"))
      (node (ref "R57") (pin "1") (pinfunction "1_1") (pintype "passive"))
      (node (ref "R58") (pin "1") (pinfunction "1_1") (pintype "passive"))
      (node (ref "R59") (pin "1") (pinfunction "1_1") (pintype "passive"))
      (node (ref "R60") (pin "1") (pinfunction "1_1") (pintype "passive"))
      (node (ref "RN2") (pin "1") (pinfunction "1_1") (pintype "passive"))
      (node (ref "RN4") (pin "1") (pinfunction "1_1") (pintype "passive"))
      (node (ref "SJ18") (pin "P$1") (pinfunction "1_P$1") (pintype "passive"))
      (node (ref "U$1") (pin "3V3") (pinfunction "3V3_3V3") (pintype "power_in"))
      (node (ref "U1") (pin "1") (pinfunction "SER_1") (pintype "input"))
      (node (ref "U1") (pin "16") (pinfunction "VCC_16") (pintype "power_in"))
      (node (ref "U1") (pin "9") (pinfunction "CLR_9") (pintype "input"))
      (node (ref "U2") (pin "16") (pinfunction "VCC_16") (pintype "power_in"))
      (node (ref "U2") (pin "9") (pinfunction "CLR_9") (pintype "input"))
    )
    (net (code "2") (name "+5V") (class "Default")
      (node (ref "C3") (pin "1") (pinfunction "1_1") (pintype "passive"))
      (node (ref "C5") (pin "1") (pinfunction "1_1") (pintype "passive"))
      (node (ref "C8") (pin "1") (pinfunction "1_1") (pintype "passive"))
      (node (ref "C9") (pin "1") (pinfunction "1_1") (pintype "passive"))
      (node (ref "JP1") (pin "3") (pinfunction "3_3") (pintype "passive"))
      (node (ref "JP2") (pin "6") (pinfunction "6_6") (pintype "passive"))
      (node (ref "JP5") (pin "3") (pinfunction "3_3") (pintype "passive"))
      (node (ref "JP5") (pin "4") (pinfunction "4_4") (pintype "passive"))
      (node (ref "JP6") (pin "3") (pinfunction "3_3") (pintype "passive"))
      (node (ref "JP6") (pin "4") (pinfunction "4_4") (pintype "passive"))
      (node (ref "JP7") (pin "3") (pinfunction "3_3") (pintype "passive"))
      (node (ref "JP7") (pin "4") (pinfunction "4_4") (pintype "passive"))
      (node (ref "JP8") (pin "3") (pinfunction "3_3") (pintype "passive"))
      (node (ref "JP8") (pin "4") (pinfunction "4_4") (pintype "passive"))
      (node (ref "PORTA") (pin "6") (pinfunction "6_6") (pintype "passive"))
      (node (ref "PORTB") (pin "6") (pinfunction "6_6") (pintype "passive"))
      (node (ref "PORTC") (pin "6") (pinfunction "6_6") (pintype "passive"))
      (node (ref "R19") (pin "2") (pinfunction "2_2") (pintype "passive"))
      (node (ref "R20") (pin "2") (pinfunction "2_2") (pintype "passive"))
      (node (ref "R21") (pin "2") (pinfunction "2_2") (pintype "passive"))
      (node (ref "R22") (pin "1") (pinfunction "1_1") (pintype "passive"))
      (node (ref "R23") (pin "1") (pinfunction "1_1") (pintype "passive"))
      (node (ref "R24") (pin "1") (pinfunction "1_1") (pintype "passive"))
      (node (ref "R25") (pin "1") (pinfunction "1_1") (pintype "passive"))
      (node (ref "R26") (pin "1") (pinfunction "1_1") (pintype "passive"))
      (node (ref "R27") (pin "1") (pinfunction "1_1") (pintype "passive"))
      (node (ref "R62") (pin "1") (pinfunction "1_1") (pintype "passive"))
      (node (ref "R63") (pin "1") (pinfunction "1_1") (pintype "passive"))
      (node (ref "R64") (pin "1") (pinfunction "1_1") (pintype "passive"))
      (node (ref "R65") (pin "1") (pinfunction "1_1") (pintype "passive"))
      (node (ref "R66") (pin "1") (pinfunction "1_1") (pintype "passive"))
      (node (ref "R67") (pin "1") (pinfunction "1_1") (pintype "passive"))
      (node (ref "SJ1") (pin "P$2") (pinfunction "2_P$2") (pintype "passive"))
      (node (ref "SJ10") (pin "P$2") (pinfunction "2_P$2") (pintype "passive"))
      (node (ref "SJ4") (pin "P$2") (pinfunction "2_P$2") (pintype "passive"))
      (node (ref "SJ7") (pin "P$2") (pinfunction "2_P$2") (pintype "passive"))
      (node (ref "U$1") (pin "5V2") (pinfunction "5V2_5V2") (pintype "power_in"))
      (node (ref "U11") (pin "10") (pinfunction "SCL_10") (pintype "input"))
      (node (ref "U11") (pin "16") (pinfunction "VCC_16") (pintype "power_in"))
      (node (ref "U13") (pin "10") (pinfunction "SCL_10") (pintype "input"))
      (node (ref "U13") (pin "16") (pinfunction "VCC_16") (pintype "power_in"))
      (node (ref "U7") (pin "3") (pinfunction "VCC_3") (pintype "power_in"))
      (node (ref "U7B") (pin "3") (pinfunction "VDD_3") (pintype "power_in"))
      (node (ref "X6") (pin "1") (pinfunction "1_1") (pintype "passive"))
    )
    (net (code "3") (name "+12V") (class "Default")
      (node (ref "C10") (pin "1") (pinfunction "1_1") (pintype "passive"))
      (node (ref "C6") (pin "1") (pinfunction "1_1") (pintype "passive"))
      (node (ref "C7") (pin "1") (pinfunction "1_1") (pintype "passive"))
      (node (ref "J3") (pin "1") (pinfunction "1_1") (pintype "passive"))
      (node (ref "JP2") (pin "7") (pinfunction "7_7") (pintype "passive"))
      (node (ref "JP4") (pin "2") (pinfunction "2_2") (pintype "passive"))
      (node (ref "SJ11") (pin "P$2") (pinfunction "2_P$2") (pintype "passive"))
      (node (ref "SJ14") (pin "P$2") (pinfunction "2_P$2") (pintype "passive"))
      (node (ref "SJ2") (pin "P$2") (pinfunction "2_P$2") (pintype "passive"))
      (node (ref "SJ5") (pin "P$2") (pinfunction "2_P$2") (pintype "passive"))
      (node (ref "SJ8") (pin "P$2") (pinfunction "2_P$2") (pintype "passive"))
      (node (ref "U10") (pin "4") (pinfunction "V+_4") (pintype "power_in"))
      (node (ref "U3") (pin "6") (pinfunction "VDD_6") (pintype "power_in"))
      (node (ref "U4") (pin "6") (pinfunction "VDD_6") (pintype "power_in"))
      (node (ref "U5") (pin "6") (pinfunction "VDD_6") (pintype "power_in"))
      (node (ref "U6") (pin "6") (pinfunction "VDD_6") (pintype "power_in"))
      (node (ref "U8") (pin "1") (pinfunction "VIN_1") (pintype "bidirectional"))
      (node (ref "U8B") (pin "5") (pinfunction "IN_5") (pintype "input"))
      (node (ref "U9") (pin "4") (pinfunction "V+_4") (pintype "power_in"))
    )
    (net (code "4") (name "/AGND") (class "Default")
      (node (ref "U$1") (pin "AGND") (pinfunction "AGND_AGND") (pintype "power_in"))
    )
    (net (code "5") (name "/AVDD") (class "Default")
      (node (ref "U$1") (pin "AVDD") (pinfunction "AVDD_AVDD") (pintype "power_in"))
    )
    (net (code "6") (name "/CANH") (class "Default")
      (node (ref "J1") (pin "1") (pinfunction "1_1") (pintype "passive"))
      (node (ref "J2") (pin "1") (pinfunction "1_1") (pintype "passive"))
      (node (ref "U7") (pin "7") (pinfunction "CANH_7") (pintype "bidirectional"))
      (node (ref "U7B") (pin "7") (pinfunction "CANH_7") (pintype "bidirectional"))
    )
    (net (code "7") (name "/CANL") (class "Default")
      (node (ref "J1") (pin "2") (pinfunction "2_2") (pintype "passive"))
      (node (ref "J2") (pin "2") (pinfunction "2_2") (pintype "passive"))
      (node (ref "U7") (pin "6") (pinfunction "CANL_6") (pintype "bidirectional"))
      (node (ref "U7B") (pin "6") (pinfunction "CANL_6") (pintype "bidirectional"))
    )
    (net (code "8") (name "/GND4") (class "Default")
      (node (ref "U$1") (pin "GND4") (pinfunction "GND4_GND4") (pintype "power_in"))
    )
    (net (code "9") (name "/PWR_POS") (class "Default")
      (node (ref "J1") (pin "8") (pinfunction "8_8") (pintype "passive"))
      (node (ref "J2") (pin "8") (pinfunction "8_8") (pintype "passive"))
      (node (ref "R40") (pin "2") (pinfunction "2_2") (pintype "passive"))
    )
    (net (code "10") (name "/U5V") (class "Default")
      (node (ref "U$1") (pin "U5V") (pinfunction "U5V_U5V") (pintype "power_in"))
    )
    (net (code "11") (name "/VBAT") (class "Default")
      (node (ref "U$1") (pin "VBAT") (pinfunction "VBAT_VBAT") (pintype "power_in"))
    )
    (net (code "12") (name "/VDD") (class "Default")
      (node (ref "U$1") (pin "VDD") (pinfunction "VDD_VDD") (pintype "power_in"))
    )
    (net (code "13") (name "CANRX") (class "Default")
      (node (ref "U$1") (pin "PB8") (pinfunction "PB8_PB8") (pintype "bidirectional"))
      (node (ref "U7") (pin "4") (pinfunction "RXD_4") (pintype "output"))
      (node (ref "U7B") (pin "4") (pinfunction "RXD_4") (pintype "bidirectional"))
    )
    (net (code "14") (name "CANTX") (class "Default")
      (node (ref "U$1") (pin "PB9") (pinfunction "PB9_PB9") (pintype "bidirectional"))
      (node (ref "U7") (pin "1") (pinfunction "TXD_1") (pintype "input"))
      (node (ref "U7B") (pin "1") (pinfunction "TXD_1") (pintype "bidirectional"))
    )
    (net (code "15") (name "E_CS") (class "Default")
      (node (ref "JP2") (pin "4") (pinfunction "4_4") (pintype "passive"))
      (node (ref "R23") (pin "2") (pinfunction "2_2") (pintype "passive"))
      (node (ref "U$1") (pin "PC10") (pinfunction "PC10_PC10") (pintype "bidirectional"))
    )
    (net (code "16") (name "E_LAT") (class "Default")
      (node (ref "JP2") (pin "5") (pinfunction "5_5") (pintype "passive"))
      (node (ref "R22") (pin "2") (pinfunction "2_2") (pintype "passive"))
      (node (ref "U$1") (pin "PC11") (pinfunction "PC11_PC11") (pintype "bidirectional"))
    )
    (net (code "17") (name "GND") (class "Default")
      (node (ref "C1") (pin "2") (pinfunction "2_2") (pintype "passive"))
      (node (ref "C10") (pin "2") (pinfunction "2_2") (pintype "passive"))
      (node (ref "C11") (pin "2") (pinfunction "2_2") (pintype "passive"))
      (node (ref "C2") (pin "-") (pinfunction "-_-") (pintype "passive"))
      (node (ref "C3") (pin "2") (pinfunction "2_2") (pintype "passive"))
      (node (ref "C4") (pin "2") (pinfunction "2_2") (pintype "passive"))
      (node (ref "C5") (pin "2") (pinfunction "2_2") (pintype "passive"))
      (node (ref "C6") (pin "2") (pinfunction "2_2") (pintype "passive"))
      (node (ref "C7") (pin "2") (pinfunction "2_2") (pintype "passive"))
      (node (ref "C8") (pin "2") (pinfunction "2_2") (pintype "passive"))
      (node (ref "C9") (pin "2") (pinfunction "2_2") (pintype "passive"))
      (node (ref "D1") (pin "A") (pinfunction "A_A") (pintype "passive"))
      (node (ref "D3") (pin "A") (pinfunction "A_A") (pintype "passive"))
      (node (ref "J1") (pin "3") (pinfunction "3_3") (pintype "passive"))
      (node (ref "J1") (pin "6") (pinfunction "6_6") (pintype "passive"))
      (node (ref "J1") (pin "7") (pinfunction "7_7") (pintype "passive"))
      (node (ref "J2") (pin "3") (pinfunction "3_3") (pintype "passive"))
      (node (ref "J2") (pin "6") (pinfunction "6_6") (pintype "passive"))
      (node (ref "J2") (pin "7") (pinfunction "7_7") (pintype "passive"))
      (node (ref "J3") (pin "2") (pinfunction "2_2") (pintype "passive"))
      (node (ref "J3") (pin "3") (pinfunction "3_3") (pintype "passive"))
      (node (ref "JP1") (pin "4") (pinfunction "4_4") (pintype "passive"))
      (node (ref "JP2") (pin "8") (pinfunction "8_8") (pintype "passive"))
      (node (ref "JP5") (pin "5") (pinfunction "5_5") (pintype "passive"))
      (node (ref "JP5") (pin "6") (pinfunction "6_6") (pintype "passive"))
      (node (ref "JP6") (pin "5") (pinfunction "5_5") (pintype "passive"))
      (node (ref "JP6") (pin "6") (pinfunction "6_6") (pintype "passive"))
      (node (ref "JP7") (pin "5") (pinfunction "5_5") (pintype "passive"))
      (node (ref "JP7") (pin "6") (pinfunction "6_6") (pintype "passive"))
      (node (ref "JP8") (pin "5") (pinfunction "5_5") (pintype "passive"))
      (node (ref "JP8") (pin "6") (pinfunction "6_6") (pintype "passive"))
      (node (ref "PORTA") (pin "5") (pinfunction "5_5") (pintype "passive"))
      (node (ref "PORTB") (pin "5") (pinfunction "5_5") (pintype "passive"))
      (node (ref "PORTC") (pin "5") (pinfunction "5_5") (pintype "passive"))
      (node (ref "Q1") (pin "2") (pinfunction "S_2") (pintype "passive"))
      (node (ref "Q10") (pin "2") (pinfunction "S_2") (pintype "passive"))
      (node (ref "Q11") (pin "2") (pinfunction "S_2") (pintype "passive"))
      (node (ref "Q12") (pin "2") (pinfunction "S_2") (pintype "passive"))
      (node (ref "Q13") (pin "2") (pinfunction "S_2") (pintype "passive"))
      (node (ref "Q14") (pin "2") (pinfunction "S_2") (pintype "passive"))
      (node (ref "Q15") (pin "2") (pinfunction "S_2") (pintype "passive"))
      (node (ref "Q16") (pin "2") (pinfunction "S_2") (pintype "passive"))
      (node (ref "Q2") (pin "2") (pinfunction "S_2") (pintype "passive"))
      (node (ref "Q3") (pin "2") (pinfunction "S_2") (pintype "passive"))
      (node (ref "Q4") (pin "2") (pinfunction "S_2") (pintype "passive"))
      (node (ref "Q5") (pin "2") (pinfunction "S_2") (pintype "passive"))
      (node (ref "Q6") (pin "2") (pinfunction "S_2") (pintype "passive"))
      (node (ref "Q7") (pin "2") (pinfunction "S_2") (pintype "passive"))
      (node (ref "Q8") (pin "2") (pinfunction "S_2") (pintype "passive"))
      (node (ref "Q9") (pin "2") (pinfunction "S_2") (pintype "passive"))
      (node (ref "R2") (pin "1") (pinfunction "1_1") (pintype "passive"))
      (node (ref "R61") (pin "2") (pinfunction "2_2") (pintype "passive"))
      (node (ref "SJ12") (pin "P$2") (pinfunction "2_P$2") (pintype "passive"))
      (node (ref "SJ3") (pin "2") (pinfunction "2_2") (pintype "passive"))
      (node (ref "SJ6") (pin "P$2") (pinfunction "2_P$2") (pintype "passive"))
      (node (ref "SJ9") (pin "2") (pinfunction "2_2") (pintype "passive"))
      (node (ref "U$1") (pin "GND3") (pinfunction "GND3_GND3") (pintype "power_in"))
      (node (ref "U$1") (pin "GND5") (pinfunction "GND5_GND5") (pintype "power_in"))
      (node (ref "U$1") (pin "GND6") (pinfunction "GND6_GND6") (pintype "power_in"))
      (node (ref "U$1") (pin "GND7") (pinfunction "GND7_GND7") (pintype "power_in"))
      (node (ref "U$1") (pin "GND8") (pinfunction "GND8_GND8") (pintype "power_in"))
      (node (ref "U1") (pin "6") (pinfunction "INH_6") (pintype "input"))
      (node (ref "U1") (pin "8") (pinfunction "GND_8") (pintype "power_in"))
      (node (ref "U10") (pin "11") (pinfunction "V-_11") (pintype "power_in"))
      (node (ref "U11") (pin "13") (pinfunction "G_13") (pintype "input"))
      (node (ref "U11") (pin "8") (pinfunction "GND_8") (pintype "power_in"))
      (node (ref "U13") (pin "13") (pinfunction "G_13") (pintype "input"))
      (node (ref "U13") (pin "8") (pinfunction "GND_8") (pintype "power_in"))
      (node (ref "U2") (pin "6") (pinfunction "INH_6") (pintype "input"))
      (node (ref "U2") (pin "8") (pinfunction "GND_8") (pintype "power_in"))
      (node (ref "U3") (pin "3") (pinfunction "VSS_3") (pintype "power_in"))
      (node (ref "U4") (pin "3") (pinfunction "VSS_3") (pintype "power_in"))
      (node (ref "U5") (pin "3") (pinfunction "VSS_3") (pintype "power_in"))
      (node (ref "U6") (pin "3") (pinfunction "VSS_3") (pintype "power_in"))
      (node (ref "U7") (pin "2") (pinfunction "GND_2") (pintype "power_in"))
      (node (ref "U7B") (pin "2") (pinfunction "VSS_2") (pintype "power_in"))
      (node (ref "U8") (pin "4") (pinfunction "SD_4") (pintype "bidirectional"))
      (node (ref "U8") (pin "5") (pinfunction "GND1_5") (pintype "power_in"))
      (node (ref "U8") (pin "6") (pinfunction "GND2_6") (pintype "power_in"))
      (node (ref "U8") (pin "7") (pinfunction "GND3_7") (pintype "power_in"))
      (node (ref "U8") (pin "8") (pinfunction "GND4_8") (pintype "power_in"))
      (node (ref "U8B") (pin "2") (pinfunction "GNDSIG_2") (pintype "input"))
      (node (ref "U8B") (pin "3") (pinfunction "~{ON/OFF}_3") (pintype "input"))
      (node (ref "U8B") (pin "4") (pinfunction "GND_4") (pintype "power_in"))
      (node (ref "U9") (pin "11") (pinfunction "V-_11") (pintype "power_in"))
      (node (ref "X6") (pin "2") (pinfunction "2_2") (pintype "passive"))
    )
    (net (code "18") (name "I2CSCL") (class "Default")
      (node (ref "JP1") (pin "1") (pinfunction "1_1") (pintype "passive"))
      (node (ref "R62") (pin "2") (pinfunction "2_2") (pintype "passive"))
      (node (ref "U$1") (pin "PB6") (pinfunction "PB6_PB6") (pintype "bidirectional"))
    )
    (net (code "19") (name "I2CSDA") (class "Default")
      (node (ref "JP1") (pin "2") (pinfunction "2_2") (pintype "passive"))
      (node (ref "R63") (pin "2") (pinfunction "2_2") (pintype "passive"))
      (node (ref "U$1") (pin "PB7") (pinfunction "PB7_PB7") (pintype "bidirectional"))
    )
    (net (code "20") (name "ILAT") (class "Default")
      (node (ref "U$1") (pin "PA6") (pinfunction "PA6_PA6") (pintype "bidirectional"))
      (node (ref "U1") (pin "15") (pinfunction "SH/~{LD}_15") (pintype "input"))
      (node (ref "U2") (pin "15") (pinfunction "SH/~{LD}_15") (pintype "input"))
    )
    (net (code "21") (name "MISO") (class "Default")
      (node (ref "JP2") (pin "1") (pinfunction "1_1") (pintype "passive"))
      (node (ref "U$1") (pin "PB4") (pinfunction "PB4_PB4") (pintype "bidirectional"))
    )
    (net (code "22") (name "MISO2") (class "Default")
      (node (ref "SJ13") (pin "P$2") (pinfunction "2_P$2") (pintype "passive"))
      (node (ref "SJ19") (pin "P$2") (pinfunction "2_P$2") (pintype "passive"))
      (node (ref "U$1") (pin "PC2") (pinfunction "PC2_PC2") (pintype "bidirectional"))
      (node (ref "U2") (pin "13") (pinfunction "QH_13") (pintype "output"))
    )
    (net (code "23") (name "MOSI") (class "Default")
      (node (ref "R20") (pin "1") (pinfunction "1_1") (pintype "passive"))
      (node (ref "SJ15") (pin "1") (pinfunction "1_1") (pintype "passive"))
      (node (ref "SJ17") (pin "P$2") (pinfunction "2_P$2") (pintype "passive"))
      (node (ref "U$1") (pin "PB5") (pinfunction "PB5_PB5") (pintype "bidirectional"))
      (node (ref "U11") (pin "14") (pinfunction "SER_14") (pintype "input"))
    )
    (net (code "24") (name "Net-(D2-PadA)") (class "Default")
      (node (ref "D2") (pin "A") (pinfunction "A_A") (pintype "passive"))
      (node (ref "D4") (pin "A") (pinfunction "A_A") (pintype "passive"))
      (node (ref "JP4") (pin "4") (pinfunction "4_4") (pintype "passive"))
    )
    (net (code "25") (name "Net-(D2-PadC)") (class "Default")
      (node (ref "D2") (pin "C") (pinfunction "C_C") (pintype "passive"))
      (node (ref "D4") (pin "C") (pinfunction "C_C") (pintype "passive"))
      (node (ref "JP4") (pin "1") (pinfunction "1_1") (pintype "passive"))
    )
    (net (code "26") (name "Net-(J1-Pad4)") (class "Default")
      (node (ref "J1") (pin "4") (pinfunction "4_4") (pintype "passive"))
      (node (ref "J2") (pin "4") (pinfunction "4_4") (pintype "passive"))
    )
    (net (code "27") (name "Net-(J1-Pad5)") (class "Default")
      (node (ref "J1") (pin "5") (pinfunction "5_5") (pintype "passive"))
      (node (ref "J2") (pin "5") (pinfunction "5_5") (pintype "passive"))
    )
    (net (code "28") (name "Net-(JP4-Pad3)") (class "Default")
      (node (ref "JP4") (pin "3") (pinfunction "3_3") (pintype "passive"))
      (node (ref "R40") (pin "1") (pinfunction "1_1") (pintype "passive"))
    )
    (net (code "29") (name "Net-(PORTA-Pad1)") (class "Default")
      (node (ref "PORTA") (pin "1") (pinfunction "1_1") (pintype "passive"))
      (node (ref "R44") (pin "2") (pinfunction "2_2") (pintype "passive"))
      (node (ref "R53") (pin "2") (pinfunction "2_2") (pintype "passive"))
      (node (ref "RN3") (pin "1") (pinfunction "1_1") (pintype "passive"))
      (node (ref "RN4") (pin "9") (pinfunction "9_9") (pintype "passive"))
      (node (ref "X1") (pin "1") (pinfunction "1_1") (pintype "passive"))
    )
    (net (code "30") (name "Net-(PORTB-Pad1)") (class "Default")
      (node (ref "PORTB") (pin "1") (pinfunction "1_1") (pintype "passive"))
      (node (ref "R35") (pin "2") (pinfunction "2_2") (pintype "passive"))
      (node (ref "R45") (pin "2") (pinfunction "2_2") (pintype "passive"))
      (node (ref "RN1") (pin "1") (pinfunction "1_1") (pintype "passive"))
      (node (ref "RN2") (pin "9") (pinfunction "9_9") (pintype "passive"))
      (node (ref "X2") (pin "1") (pinfunction "1_1") (pintype "passive"))
    )
    (net (code "31") (name "Net-(Q1-D)") (class "Default")
      (node (ref "Q1") (pin "3") (pinfunction "D_3") (pintype "passive"))
      (node (ref "U12") (pin "18") (pinfunction "O1_18") (pintype "open_collector"))
      (node (ref "X5") (pin "1") (pinfunction "1_1") (pintype "passive"))
    )
    (net (code "32") (name "Net-(Q1-G)") (class "Default")
      (node (ref "Q1") (pin "1") (pinfunction "G_1") (pintype "passive"))
      (node (ref "R3") (pin "2") (pinfunction "2_2") (pintype "passive"))
    )
    (net (code "33") (name "Net-(Q2-D)") (class "Default")
      (node (ref "Q2") (pin "3") (pinfunction "D_3") (pintype "passive"))
      (node (ref "U12") (pin "17") (pinfunction "O2_17") (pintype "open_collector"))
      (node (ref "X5") (pin "2") (pinfunction "2_2") (pintype "passive"))
    )
    (net (code "34") (name "Net-(Q2-G)") (class "Default")
      (node (ref "Q2") (pin "1") (pinfunction "G_1") (pintype "passive"))
      (node (ref "R4") (pin "2") (pinfunction "2_2") (pintype "passive"))
    )
    (net (code "35") (name "Net-(Q3-D)") (class "Default")
      (node (ref "Q3") (pin "3") (pinfunction "D_3") (pintype "passive"))
      (node (ref "U12") (pin "16") (pinfunction "O3_16") (pintype "open_collector"))
      (node (ref "X5") (pin "3") (pinfunction "3_3") (pintype "passive"))
    )
    (net (code "36") (name "Net-(Q3-G)") (class "Default")
      (node (ref "Q3") (pin "1") (pinfunction "G_1") (pintype "passive"))
      (node (ref "R5") (pin "2") (pinfunction "2_2") (pintype "passive"))
    )
    (net (code "37") (name "Net-(Q4-D)") (class "Default")
      (node (ref "Q4") (pin "3") (pinfunction "D_3") (pintype "passive"))
      (node (ref "U12") (pin "15") (pinfunction "O4_15") (pintype "open_collector"))
      (node (ref "X5") (pin "4") (pinfunction "4_4") (pintype "passive"))
    )
    (net (code "38") (name "Net-(Q4-G)") (class "Default")
      (node (ref "Q4") (pin "1") (pinfunction "G_1") (pintype "passive"))
      (node (ref "R6") (pin "2") (pinfunction "2_2") (pintype "passive"))
    )
    (net (code "39") (name "Net-(Q5-D)") (class "Default")
      (node (ref "Q5") (pin "3") (pinfunction "D_3") (pintype "passive"))
      (node (ref "U12") (pin "14") (pinfunction "O5_14") (pintype "open_collector"))
      (node (ref "X5") (pin "5") (pinfunction "5_5") (pintype "passive"))
    )
    (net (code "40") (name "Net-(Q5-G)") (class "Default")
      (node (ref "Q5") (pin "1") (pinfunction "G_1") (pintype "passive"))
      (node (ref "R7") (pin "2") (pinfunction "2_2") (pintype "passive"))
    )
    (net (code "41") (name "Net-(Q6-D)") (class "Default")
      (node (ref "Q6") (pin "3") (pinfunction "D_3") (pintype "passive"))
      (node (ref "U12") (pin "13") (pinfunction "O6_13") (pintype "open_collector"))
      (node (ref "X5") (pin "6") (pinfunction "6_6") (pintype "passive"))
    )
    (net (code "42") (name "Net-(Q6-G)") (class "Default")
      (node (ref "Q6") (pin "1") (pinfunction "G_1") (pintype "passive"))
      (node (ref "R8") (pin "2") (pinfunction "2_2") (pintype "passive"))
    )
    (net (code "43") (name "Net-(Q7-D)") (class "Default")
      (node (ref "Q7") (pin "3") (pinfunction "D_3") (pintype "passive"))
      (node (ref "U12") (pin "12") (pinfunction "O7_12") (pintype "open_collector"))
      (node (ref "X5") (pin "7") (pinfunction "7_7") (pintype "passive"))
    )
    (net (code "44") (name "Net-(Q7-G)") (class "Default")
      (node (ref "Q7") (pin "1") (pinfunction "G_1") (pintype "passive"))
      (node (ref "R9") (pin "2") (pinfunction "2_2") (pintype "passive"))
    )
    (net (code "45") (name "Net-(Q8-D)") (class "Default")
      (node (ref "Q8") (pin "3") (pinfunction "D_3") (pintype "passive"))
      (node (ref "U12") (pin "11") (pinfunction "O8_11") (pintype "open_collector"))
      (node (ref "X5") (pin "8") (pinfunction "8_8") (pintype "passive"))
    )
    (net (code "46") (name "Net-(Q8-G)") (class "Default")
      (node (ref "Q8") (pin "1") (pinfunction "G_1") (pintype "passive"))
      (node (ref "R10") (pin "2") (pinfunction "2_2") (pintype "passive"))
    )
    (net (code "47") (name "Net-(Q9-D)") (class "Default")
      (node (ref "Q9") (pin "3") (pinfunction "D_3") (pintype "passive"))
      (node (ref "U14") (pin "18") (pinfunction "O1_18") (pintype "open_collector"))
      (node (ref "X4") (pin "1") (pinfunction "1_1") (pintype "passive"))
    )
    (net (code "48") (name "Net-(Q9-G)") (class "Default")
      (node (ref "Q9") (pin "1") (pinfunction "G_1") (pintype "passive"))
      (node (ref "R11") (pin "2") (pinfunction "2_2") (pintype "passive"))
    )
    (net (code "49") (name "Net-(Q10-D)") (class "Default")
      (node (ref "Q10") (pin "3") (pinfunction "D_3") (pintype "passive"))
      (node (ref "U14") (pin "17") (pinfunction "O2_17") (pintype "open_collector"))
      (node (ref "X4") (pin "2") (pinfunction "2_2") (pintype "passive"))
    )
    (net (code "50") (name "Net-(Q10-G)") (class "Default")
      (node (ref "Q10") (pin "1") (pinfunction "G_1") (pintype "passive"))
      (node (ref "R12") (pin "2") (pinfunction "2_2") (pintype "passive"))
    )
    (net (code "51") (name "Net-(Q11-D)") (class "Default")
      (node (ref "Q11") (pin "3") (pinfunction "D_3") (pintype "passive"))
      (node (ref "U14") (pin "16") (pinfunction "O3_16") (pintype "open_collector"))
      (node (ref "X4") (pin "3") (pinfunction "3_3") (pintype "passive"))
    )
    (net (code "52") (name "Net-(Q11-G)") (class "Default")
      (node (ref "Q11") (pin "1") (pinfunction "G_1") (pintype "passive"))
      (node (ref "R13") (pin "2") (pinfunction "2_2") (pintype "passive"))
    )
    (net (code "53") (name "Net-(Q12-D)") (class "Default")
      (node (ref "Q12") (pin "3") (pinfunction "D_3") (pintype "passive"))
      (node (ref "U14") (pin "15") (pinfunction "O4_15") (pintype "open_collector"))
      (node (ref "X4") (pin "4") (pinfunction "4_4") (pintype "passive"))
    )
    (net (code "54") (name "Net-(Q12-G)") (class "Default")
      (node (ref "Q12") (pin "1") (pinfunction "G_1") (pintype "passive"))
      (node (ref "R14") (pin "2") (pinfunction "2_2") (pintype "passive"))
    )
    (net (code "55") (name "Net-(Q13-D)") (class "Default")
      (node (ref "Q13") (pin "3") (pinfunction "D_3") (pintype "passive"))
      (node (ref "U14") (pin "14") (pinfunction "O5_14") (pintype "open_collector"))
      (node (ref "X4") (pin "5") (pinfunction "5_5") (pintype "passive"))
    )
    (net (code "56") (name "Net-(Q13-G)") (class "Default")
      (node (ref "Q13") (pin "1") (pinfunction "G_1") (pintype "passive"))
      (node (ref "R15") (pin "2") (pinfunction "2_2") (pintype "passive"))
    )
    (net (code "57") (name "Net-(Q14-D)") (class "Default")
      (node (ref "Q14") (pin "3") (pinfunction "D_3") (pintype "passive"))
      (node (ref "U14") (pin "13") (pinfunction "O6_13") (pintype "open_collector"))
      (node (ref "X4") (pin "6") (pinfunction "6_6") (pintype "passive"))
    )
    (net (code "58") (name "Net-(Q14-G)") (class "Default")
      (node (ref "Q14") (pin "1") (pinfunction "G_1") (pintype "passive"))
      (node (ref "R16") (pin "2") (pinfunction "2_2") (pintype "passive"))
    )
    (net (code "59") (name "Net-(Q15-D)") (class "Default")
      (node (ref "Q15") (pin "3") (pinfunction "D_3") (pintype "passive"))
      (node (ref "U14") (pin "12") (pinfunction "O7_12") (pintype "open_collector"))
      (node (ref "X4") (pin "7") (pinfunction "7_7") (pintype "passive"))
    )
    (net (code "60") (name "Net-(Q15-G)") (class "Default")
      (node (ref "Q15") (pin "1") (pinfunction "G_1") (pintype "passive"))
      (node (ref "R17") (pin "2") (pinfunction "2_2") (pintype "passive"))
    )
    (net (code "61") (name "Net-(Q16-D)") (class "Default")
      (node (ref "Q16") (pin "3") (pinfunction "D_3") (pintype "passive"))
      (node (ref "U14") (pin "11") (pinfunction "O8_11") (pintype "open_collector"))
      (node (ref "X4") (pin "8") (pinfunction "8_8") (pintype "passive"))
    )
    (net (code "62") (name "Net-(Q16-G)") (class "Default")
      (node (ref "Q16") (pin "1") (pinfunction "G_1") (pintype "passive"))
      (node (ref "R18") (pin "2") (pinfunction "2_2") (pintype "passive"))
    )
    (net (code "63") (name "Net-(RN1A-2)") (class "Default")
      (node (ref "R35") (pin "1") (pinfunction "1_1") (pintype "passive"))
      (node (ref "RN1") (pin "16") (pinfunction "2_16") (pintype "passive"))
      (node (ref "U2") (pin "14") (pinfunction "H_14") (pintype "input"))
    )
    (net (code "64") (name "Net-(RN1B-1)") (class "Default")
      (node (ref "PORTB") (pin "2") (pinfunction "2_2") (pintype "passive"))
      (node (ref "R34") (pin "2") (pinfunction "2_2") (pintype "passive"))
      (node (ref "R46") (pin "2") (pinfunction "2_2") (pintype "passive"))
      (node (ref "RN1") (pin "2") (pinfunction "1_2") (pintype "passive"))
      (node (ref "RN2") (pin "8") (pinfunction "8_8") (pintype "passive"))
      (node (ref "X2") (pin "2") (pinfunction "2_2") (pintype "passive"))
    )
    (net (code "65") (name "Net-(RN1B-2)") (class "Default")
      (node (ref "R34") (pin "1") (pinfunction "1_1") (pintype "passive"))
      (node (ref "RN1") (pin "15") (pinfunction "2_15") (pintype "passive"))
      (node (ref "U2") (pin "12") (pinfunction "G_12") (pintype "input"))
    )
    (net (code "66") (name "Net-(RN1C-1)") (class "Default")
      (node (ref "PORTB") (pin "3") (pinfunction "3_3") (pintype "passive"))
      (node (ref "R33") (pin "2") (pinfunction "2_2") (pintype "passive"))
      (node (ref "R47") (pin "2") (pinfunction "2_2") (pintype "passive"))
      (node (ref "RN1") (pin "3") (pinfunction "1_3") (pintype "passive"))
      (node (ref "RN2") (pin "7") (pinfunction "7_7") (pintype "passive"))
      (node (ref "X2") (pin "3") (pinfunction "3_3") (pintype "passive"))
    )
    (net (code "67") (name "Net-(RN1C-2)") (class "Default")
      (node (ref "R33") (pin "1") (pinfunction "1_1") (pintype "passive"))
      (node (ref "RN1") (pin "14") (pinfunction "2_14") (pintype "passive"))
      (node (ref "U2") (pin "11") (pinfunction "F_11") (pintype "input"))
    )
    (net (code "68") (name "Net-(RN1D-1)") (class "Default")
      (node (ref "PORTB") (pin "4") (pinfunction "4_4") (pintype "passive"))
      (node (ref "R32") (pin "2") (pinfunction "2_2") (pintype "passive"))
      (node (ref "R48") (pin "2") (pinfunction "2_2") (pintype "passive"))
      (node (ref "RN1") (pin "4") (pinfunction "1_4") (pintype "passive"))
      (node (ref "RN2") (pin "6") (pinfunction "6_6") (pintype "passive"))
      (node (ref "X2") (pin "4") (pinfunction "4_4") (pintype "passive"))
    )
    (net (code "69") (name "Net-(RN1D-2)") (class "Default")
      (node (ref "R32") (pin "1") (pinfunction "1_1") (pintype "passive"))
      (node (ref "RN1") (pin "13") (pinfunction "2_13") (pintype "passive"))
      (node (ref "U2") (pin "10") (pinfunction "E_10") (pintype "input"))
    )
    (net (code "70") (name "Net-(RN1E-1)") (class "Default")
      (node (ref "PORTB") (pin "7") (pinfunction "7_7") (pintype "passive"))
      (node (ref "R31") (pin "2") (pinfunction "2_2") (pintype "passive"))
      (node (ref "R49") (pin "2") (pinfunction "2_2") (pintype "passive"))
      (node (ref "RN1") (pin "5") (pinfunction "1_5") (pintype "passive"))
      (node (ref "RN2") (pin "5") (pinfunction "5_5") (pintype "passive"))
      (node (ref "X2") (pin "5") (pinfunction "5_5") (pintype "passive"))
    )
    (net (code "71") (name "Net-(RN1E-2)") (class "Default")
      (node (ref "R31") (pin "1") (pinfunction "1_1") (pintype "passive"))
      (node (ref "RN1") (pin "12") (pinfunction "2_12") (pintype "passive"))
      (node (ref "U2") (pin "5") (pinfunction "D_5") (pintype "input"))
    )
    (net (code "72") (name "Net-(RN1F-1)") (class "Default")
      (node (ref "PORTB") (pin "8") (pinfunction "8_8") (pintype "passive"))
      (node (ref "R30") (pin "2") (pinfunction "2_2") (pintype "passive"))
      (node (ref "R50") (pin "2") (pinfunction "2_2") (pintype "passive"))
      (node (ref "RN1") (pin "6") (pinfunction "1_6") (pintype "passive"))
      (node (ref "RN2") (pin "4") (pinfunction "4_4") (pintype "passive"))
      (node (ref "X2") (pin "6") (pinfunction "6_6") (pintype "passive"))
    )
    (net (code "73") (name "Net-(RN1F-2)") (class "Default")
      (node (ref "R30") (pin "1") (pinfunction "1_1") (pintype "passive"))
      (node (ref "RN1") (pin "11") (pinfunction "2_11") (pintype "passive"))
      (node (ref "U2") (pin "4") (pinfunction "C_4") (pintype "input"))
    )
    (net (code "74") (name "Net-(RN1G-1)") (class "Default")
      (node (ref "PORTB") (pin "9") (pinfunction "9_9") (pintype "passive"))
      (node (ref "R29") (pin "2") (pinfunction "2_2") (pintype "passive"))
      (node (ref "R51") (pin "2") (pinfunction "2_2") (pintype "passive"))
      (node (ref "RN1") (pin "7") (pinfunction "1_7") (pintype "passive"))
      (node (ref "RN2") (pin "3") (pinfunction "3_3") (pintype "passive"))
      (node (ref "X2") (pin "7") (pinfunction "7_7") (pintype "passive"))
    )
    (net (code "75") (name "Net-(RN1G-2)") (class "Default")
      (node (ref "R29") (pin "1") (pinfunction "1_1") (pintype "passive"))
      (node (ref "RN1") (pin "10") (pinfunction "2_10") (pintype "passive"))
      (node (ref "U2") (pin "3") (pinfunction "B_3") (pintype "input"))
    )
    (net (code "76") (name "Net-(RN1H-1)") (class "Default")
      (node (ref "PORTB") (pin "10") (pinfunction "10_10") (pintype "passive"))
      (node (ref "R28") (pin "2") (pinfunction "2_2") (pintype "passive"))
      (node (ref "R52") (pin "2") (pinfunction "2_2") (pintype "passive"))
      (node (ref "RN1") (pin "8") (pinfunction "1_8") (pintype "passive"))
      (node (ref "RN2") (pin "2") (pinfunction "2_2") (pintype "passive"))
      (node (ref "X2") (pin "8") (pinfunction "8_8") (pintype "passive"))
    )
    (net (code "77") (name "Net-(RN1H-2)") (class "Default")
      (node (ref "R28") (pin "1") (pinfunction "1_1") (pintype "passive"))
      (node (ref "RN1") (pin "9") (pinfunction "2_9") (pintype "passive"))
      (node (ref "U2") (pin "2") (pinfunction "A_2") (pintype "input"))
    )
    (net (code "78") (name "Net-(RN3A-2)") (class "Default")
      (node (ref "R44") (pin "1") (pinfunction "1_1") (pintype "passive"))
      (node (ref "RN3") (pin "16") (pinfunction "2_16") (pintype "passive"))
      (node (ref "U1") (pin "14") (pinfunction "H_14") (pintype "input"))
    )
    (net (code "79") (name "Net-(RN3B-1)") (class "Default")
      (node (ref "PORTA") (pin "2") (pinfunction "2_2") (pintype "passive"))
      (node (ref "R43") (pin "2") (pinfunction "2_2") (pintype "passive"))
      (node (ref "R54") (pin "2") (pinfunction "2_2") (pintype "passive"))
      (node (ref "RN3") (pin "2") (pinfunction "1_2") (pintype "passive"))
      (node (ref "RN4") (pin "8") (pinfunction "8_8") (pintype "passive"))
      (node (ref "X1") (pin "2") (pinfunction "2_2") (pintype "passive"))
    )
    (net (code "80") (name "Net-(RN3B-2)") (class "Default")
      (node (ref "R43") (pin "1") (pinfunction "1_1") (pintype "passive"))
      (node (ref "RN3") (pin "15") (pinfunction "2_15") (pintype "passive"))
      (node (ref "U1") (pin "12") (pinfunction "G_12") (pintype "input"))
    )
    (net (code "81") (name "Net-(RN3C-1)") (class "Default")
      (node (ref "PORTA") (pin "3") (pinfunction "3_3") (pintype "passive"))
      (node (ref "R42") (pin "2") (pinfunction "2_2") (pintype "passive"))
      (node (ref "R55") (pin "2") (pinfunction "2_2") (pintype "passive"))
      (node (ref "RN3") (pin "3") (pinfunction "1_3") (pintype "passive"))
      (node (ref "RN4") (pin "7") (pinfunction "7_7") (pintype "passive"))
      (node (ref "X1") (pin "3") (pinfunction "3_3") (pintype "passive"))
    )
    (net (code "82") (name "Net-(RN3C-2)") (class "Default")
      (node (ref "R42") (pin "1") (pinfunction "1_1") (pintype "passive"))
      (node (ref "RN3") (pin "14") (pinfunction "2_14") (pintype "passive"))
      (node (ref "U1") (pin "11") (pinfunction "F_11") (pintype "input"))
    )
    (net (code "83") (name "Net-(RN3D-1)") (class "Default")
      (node (ref "PORTA") (pin "4") (pinfunction "4_4") (pintype "passive"))
      (node (ref "R41") (pin "2") (pinfunction "2_2") (pintype "passive"))
      (node (ref "R56") (pin "2") (pinfunction "2_2") (pintype "passive"))
      (node (ref "RN3") (pin "4") (pinfunction "1_4") (pintype "passive"))
      (node (ref "RN4") (pin "6") (pinfunction "6_6") (pintype "passive"))
      (node (ref "X1") (pin "4") (pinfunction "4_4") (pintype "passive"))
    )
    (net (code "84") (name "Net-(RN3D-2)") (class "Default")
      (node (ref "R41") (pin "1") (pinfunction "1_1") (pintype "passive"))
      (node (ref "RN3") (pin "13") (pinfunction "2_13") (pintype "passive"))
      (node (ref "U1") (pin "10") (pinfunction "E_10") (pintype "input"))
    )
    (net (code "85") (name "Net-(RN3E-1)") (class "Default")
      (node (ref "PORTA") (pin "7") (pinfunction "7_7") (pintype "passive"))
      (node (ref "R39") (pin "2") (pinfunction "2_2") (pintype "passive"))
      (node (ref "R57") (pin "2") (pinfunction "2_2") (pintype "passive"))
      (node (ref "RN3") (pin "5") (pinfunction "1_5") (pintype "passive"))
      (node (ref "RN4") (pin "5") (pinfunction "5_5") (pintype "passive"))
      (node (ref "X1") (pin "5") (pinfunction "5_5") (pintype "passive"))
    )
    (net (code "86") (name "Net-(RN3E-2)") (class "Default")
      (node (ref "R39") (pin "1") (pinfunction "1_1") (pintype "passive"))
      (node (ref "RN3") (pin "12") (pinfunction "2_12") (pintype "passive"))
      (node (ref "U1") (pin "5") (pinfunction "D_5") (pintype "input"))
    )
    (net (code "87") (name "Net-(RN3F-1)") (class "Default")
      (node (ref "PORTA") (pin "8") (pinfunction "8_8") (pintype "passive"))
      (node (ref "R38") (pin "2") (pinfunction "2_2") (pintype "passive"))
      (node (ref "R58") (pin "2") (pinfunction "2_2") (pintype "passive"))
      (node (ref "RN3") (pin "6") (pinfunction "1_6") (pintype "passive"))
      (node (ref "RN4") (pin "4") (pinfunction "4_4") (pintype "passive"))
      (node (ref "X1") (pin "6") (pinfunction "6_6") (pintype "passive"))
    )
    (net (code "88") (name "Net-(RN3F-2)") (class "Default")
      (node (ref "R38") (pin "1") (pinfunction "1_1") (pintype "passive"))
      (node (ref "RN3") (pin "11") (pinfunction "2_11") (pintype "passive"))
      (node (ref "U1") (pin "4") (pinfunction "C_4") (pintype "input"))
    )
    (net (code "89") (name "Net-(RN3G-1)") (class "Default")
      (node (ref "PORTA") (pin "9") (pinfunction "9_9") (pintype "passive"))
      (node (ref "R37") (pin "2") (pinfunction "2_2") (pintype "passive"))
      (node (ref "R59") (pin "2") (pinfunction "2_2") (pintype "passive"))
      (node (ref "RN3") (pin "7") (pinfunction "1_7") (pintype "passive"))
      (node (ref "RN4") (pin "3") (pinfunction "3_3") (pintype "passive"))
      (node (ref "X1") (pin "7") (pinfunction "7_7") (pintype "passive"))
    )
    (net (code "90") (name "Net-(RN3G-2)") (class "Default")
      (node (ref "R37") (pin "1") (pinfunction "1_1") (pintype "passive"))
      (node (ref "RN3") (pin "10") (pinfunction "2_10") (pintype "passive"))
      (node (ref "U1") (pin "3") (pinfunction "B_3") (pintype "input"))
    )
    (net (code "91") (name "Net-(RN3H-1)") (class "Default")
      (node (ref "PORTA") (pin "10") (pinfunction "10_10") (pintype "passive"))
      (node (ref "R36") (pin "2") (pinfunction "2_2") (pintype "passive"))
      (node (ref "R60") (pin "2") (pinfunction "2_2") (pintype "passive"))
      (node (ref "RN3") (pin "8") (pinfunction "1_8") (pintype "passive"))
      (node (ref "RN4") (pin "2") (pinfunction "2_2") (pintype "passive"))
      (node (ref "X1") (pin "8") (pinfunction "8_8") (pintype "passive"))
    )
    (net (code "92") (name "Net-(RN3H-2)") (class "Default")
      (node (ref "R36") (pin "1") (pinfunction "1_1") (pintype "passive"))
      (node (ref "RN3") (pin "9") (pinfunction "2_9") (pintype "passive"))
      (node (ref "U1") (pin "2") (pinfunction "A_2") (pintype "input"))
    )
    (net (code "93") (name "Net-(SJ1-1)") (class "Default")
      (node (ref "SJ1") (pin "P$1") (pinfunction "1_P$1") (pintype "passive"))
      (node (ref "SJ2") (pin "P$1") (pinfunction "1_P$1") (pintype "passive"))
      (node (ref "SJ3") (pin "1") (pinfunction "1_1") (pintype "passive"))
      (node (ref "U12") (pin "9") (pinfunction "GND_9") (pintype "power_in"))
    )
    (net (code "94") (name "Net-(SJ4-1)") (class "Default")
      (node (ref "SJ4") (pin "P$1") (pinfunction "1_P$1") (pintype "passive"))
      (node (ref "SJ5") (pin "P$1") (pinfunction "1_P$1") (pintype "passive"))
      (node (ref "SJ6") (pin "P$1") (pinfunction "1_P$1") (pintype "passive"))
      (node (ref "U12") (pin "10") (pinfunction "CD+_10") (pintype "passive"))
    )
    (net (code "95") (name "Net-(SJ7-1)") (class "Default")
      (node (ref "SJ7") (pin "P$1") (pinfunction "1_P$1") (pintype "passive"))
      (node (ref "SJ8") (pin "P$1") (pinfunction "1_P$1") (pintype "passive"))
      (node (ref "SJ9") (pin "1") (pinfunction "1_1") (pintype "passive"))
      (node (ref "U14") (pin "9") (pinfunction "GND_9") (pintype "power_in"))
    )
    (net (code "96") (name "Net-(SJ10-1)") (class "Default")
      (node (ref "SJ10") (pin "P$1") (pinfunction "1_P$1") (pintype "passive"))
      (node (ref "SJ11") (pin "P$1") (pinfunction "1_P$1") (pintype "passive"))
      (node (ref "SJ12") (pin "P$1") (pinfunction "1_P$1") (pintype "passive"))
      (node (ref "U14") (pin "10") (pinfunction "CD+_10") (pintype "passive"))
    )
    (net (code "97") (name "Net-(SJ13-1)") (class "Default")
      (node (ref "SJ13") (pin "P$1") (pinfunction "1_P$1") (pintype "passive"))
      (node (ref "U$1") (pin "PB14") (pinfunction "PB14_PB14") (pintype "bidirectional"))
    )
    (net (code "98") (name "Net-(SJ14-1)") (class "Default")
      (node (ref "SJ14") (pin "P$1") (pinfunction "1_P$1") (pintype "passive"))
      (node (ref "U$1") (pin "VIN2") (pinfunction "VIN2_VIN2") (pintype "power_in"))
    )
    (net (code "99") (name "Net-(SJ16-2)") (class "Default")
      (node (ref "JP2") (pin "2") (pinfunction "2_2") (pintype "passive"))
      (node (ref "SJ15") (pin "2") (pinfunction "2_2") (pintype "passive"))
      (node (ref "SJ16") (pin "P$2") (pinfunction "2_P$2") (pintype "passive"))
    )
    (net (code "100") (name "Net-(SJ18-2)") (class "Default")
      (node (ref "SJ18") (pin "P$2") (pinfunction "2_P$2") (pintype "passive"))
      (node (ref "U7") (pin "5") (pinfunction "VREF_5") (pintype "output"))
      (node (ref "U7B") (pin "5") (pinfunction "VREF_5") (pintype "bidirectional"))
    )
    (net (code "101") (name "Net-(U3A-O)") (class "Default")
      (node (ref "PORTC") (pin "1") (pinfunction "1_1") (pintype "passive"))
      (node (ref "U3") (pin "7") (pinfunction "O_7") (pintype "output"))
      (node (ref "U9") (pin "7") (pinfunction "OUT_7") (pintype "output"))
      (node (ref "X3") (pin "1") (pinfunction "1_1") (pintype "passive"))
    )
    (net (code "102") (name "Net-(U3B-O)") (class "Default")
      (node (ref "PORTC") (pin "2") (pinfunction "2_2") (pintype "passive"))
      (node (ref "U3") (pin "5") (pinfunction "O_5") (pintype "output"))
      (node (ref "U9") (pin "8") (pinfunction "OUT_8") (pintype "output"))
      (node (ref "X3") (pin "2") (pinfunction "2_2") (pintype "passive"))
    )
    (net (code "103") (name "Net-(U4A-O)") (class "Default")
      (node (ref "PORTC") (pin "4") (pinfunction "4_4") (pintype "passive"))
      (node (ref "U4") (pin "7") (pinfunction "O_7") (pintype "output"))
      (node (ref "U9") (pin "14") (pinfunction "OUT_14") (pintype "output"))
      (node (ref "X3") (pin "4") (pinfunction "4_4") (pintype "passive"))
    )
    (net (code "104") (name "Net-(U4B-O)") (class "Default")
      (node (ref "PORTC") (pin "3") (pinfunction "3_3") (pintype "passive"))
      (node (ref "U4") (pin "5") (pinfunction "O_5") (pintype "output"))
      (node (ref "U9") (pin "1") (pinfunction "OUT_1") (pintype "output"))
      (node (ref "X3") (pin "3") (pinfunction "3_3") (pintype "passive"))
    )
    (net (code "105") (name "Net-(U7-RS)") (class "Default")
      (node (ref "R61") (pin "1") (pinfunction "1_1") (pintype "passive"))
      (node (ref "U7") (pin "8") (pinfunction "RS_8") (pintype "input"))
      (node (ref "U7B") (pin "8") (pinfunction "RS_8") (pintype "bidirectional"))
    )
    (net (code "106") (name "Net-(U8-VOUT)") (class "Default")
      (node (ref "D1") (pin "C") (pinfunction "C_C") (pintype "passive"))
      (node (ref "D3") (pin "C") (pinfunction "C_C") (pintype "passive"))
      (node (ref "L1") (pin "2") (pinfunction "2_2") (pintype "passive"))
      (node (ref "U8") (pin "2") (pinfunction "VOUT_2") (pintype "bidirectional"))
      (node (ref "U8B") (pin "7") (pinfunction "OUT_7") (pintype "passive"))
    )
    (net (code "107") (name "Net-(U10A--IN)") (class "Default")
      (node (ref "R1") (pin "1") (pinfunction "1_1") (pintype "passive"))
      (node (ref "R2") (pin "2") (pinfunction "2_2") (pintype "passive"))
      (node (ref "U10") (pin "13") (pinfunction "-IN_13") (pintype "input"))
      (node (ref "U10") (pin "2") (pinfunction "-IN_2") (pintype "input"))
      (node (ref "U10") (pin "6") (pinfunction "-IN_6") (pintype "input"))
      (node (ref "U10") (pin "9") (pinfunction "-IN_9") (pintype "input"))
      (node (ref "U9") (pin "13") (pinfunction "-IN_13") (pintype "input"))
      (node (ref "U9") (pin "2") (pinfunction "-IN_2") (pintype "input"))
      (node (ref "U9") (pin "6") (pinfunction "-IN_6") (pintype "input"))
      (node (ref "U9") (pin "9") (pinfunction "-IN_9") (pintype "input"))
    )
    (net (code "108") (name "Net-(U10A-OUT)") (class "Default")
      (node (ref "PORTC") (pin "9") (pinfunction "9_9") (pintype "passive"))
      (node (ref "U10") (pin "1") (pinfunction "OUT_1") (pintype "output"))
      (node (ref "U6") (pin "5") (pinfunction "O_5") (pintype "output"))
      (node (ref "X3") (pin "7") (pinfunction "7_7") (pintype "passive"))
    )
    (net (code "109") (name "Net-(U10B-OUT)") (class "Default")
      (node (ref "PORTC") (pin "7") (pinfunction "7_7") (pintype "passive"))
      (node (ref "U10") (pin "7") (pinfunction "OUT_7") (pintype "output"))
      (node (ref "U5") (pin "7") (pinfunction "O_7") (pintype "output"))
      (node (ref "X3") (pin "5") (pinfunction "5_5") (pintype "passive"))
    )
    (net (code "110") (name "Net-(U10C-OUT)") (class "Default")
      (node (ref "PORTC") (pin "8") (pinfunction "8_8") (pintype "passive"))
      (node (ref "U10") (pin "8") (pinfunction "OUT_8") (pintype "output"))
      (node (ref "U5") (pin "5") (pinfunction "O_5") (pintype "output"))
      (node (ref "X3") (pin "6") (pinfunction "6_6") (pintype "passive"))
    )
    (net (code "111") (name "Net-(U10D-OUT)") (class "Default")
      (node (ref "PORTC") (pin "10") (pinfunction "10_10") (pintype "passive"))
      (node (ref "U10") (pin "14") (pinfunction "OUT_14") (pintype "output"))
      (node (ref "U6") (pin "7") (pinfunction "O_7") (pintype "output"))
      (node (ref "X3") (pin "8") (pinfunction "8_8") (pintype "passive"))
    )
    (net (code "112") (name "Net-(U11A-QA)") (class "Default")
      (node (ref "R3") (pin "1") (pinfunction "1_1") (pintype "passive"))
      (node (ref "U11") (pin "15") (pinfunction "QA_15") (pintype "tri_state"))
      (node (ref "U12") (pin "1") (pinfunction "I1_1") (pintype "input"))
    )
    (net (code "113") (name "Net-(U11A-QB)") (class "Default")
      (node (ref "R4") (pin "1") (pinfunction "1_1") (pintype "passive"))
      (node (ref "U11") (pin "1") (pinfunction "QB_1") (pintype "tri_state"))
      (node (ref "U12") (pin "2") (pinfunction "I2_2") (pintype "input"))
    )
    (net (code "114") (name "Net-(U11A-QC)") (class "Default")
      (node (ref "R5") (pin "1") (pinfunction "1_1") (pintype "passive"))
      (node (ref "U11") (pin "2") (pinfunction "QC_2") (pintype "tri_state"))
      (node (ref "U12") (pin "3") (pinfunction "I3_3") (pintype "input"))
    )
    (net (code "115") (name "Net-(U11A-QD)") (class "Default")
      (node (ref "R6") (pin "1") (pinfunction "1_1") (pintype "passive"))
      (node (ref "U11") (pin "3") (pinfunction "QD_3") (pintype "tri_state"))
      (node (ref "U12") (pin "4") (pinfunction "I4_4") (pintype "input"))
    )
    (net (code "116") (name "Net-(U11A-QE)") (class "Default")
      (node (ref "R7") (pin "1") (pinfunction "1_1") (pintype "passive"))
      (node (ref "U11") (pin "4") (pinfunction "QE_4") (pintype "tri_state"))
      (node (ref "U12") (pin "5") (pinfunction "I5_5") (pintype "input"))
    )
    (net (code "117") (name "Net-(U11A-QF)") (class "Default")
      (node (ref "R8") (pin "1") (pinfunction "1_1") (pintype "passive"))
      (node (ref "U11") (pin "5") (pinfunction "QF_5") (pintype "tri_state"))
      (node (ref "U12") (pin "6") (pinfunction "I6_6") (pintype "input"))
    )
    (net (code "118") (name "Net-(U11A-QG)") (class "Default")
      (node (ref "R9") (pin "1") (pinfunction "1_1") (pintype "passive"))
      (node (ref "U11") (pin "6") (pinfunction "QG_6") (pintype "tri_state"))
      (node (ref "U12") (pin "7") (pinfunction "I7_7") (pintype "input"))
    )
    (net (code "119") (name "Net-(U11A-QH)") (class "Default")
      (node (ref "R10") (pin "1") (pinfunction "1_1") (pintype "passive"))
      (node (ref "U11") (pin "7") (pinfunction "QH_7") (pintype "tri_state"))
      (node (ref "U12") (pin "8") (pinfunction "I8_8") (pintype "input"))
    )
    (net (code "120") (name "Net-(U13A-QA)") (class "Default")
      (node (ref "R11") (pin "1") (pinfunction "1_1") (pintype "passive"))
      (node (ref "U13") (pin "15") (pinfunction "QA_15") (pintype "tri_state"))
      (node (ref "U14") (pin "1") (pinfunction "I1_1") (pintype "input"))
    )
    (net (code "121") (name "Net-(U13A-QB)") (class "Default")
      (node (ref "R12") (pin "1") (pinfunction "1_1") (pintype "passive"))
      (node (ref "U13") (pin "1") (pinfunction "QB_1") (pintype "tri_state"))
      (node (ref "U14") (pin "2") (pinfunction "I2_2") (pintype "input"))
    )
    (net (code "122") (name "Net-(U13A-QC)") (class "Default")
      (node (ref "R13") (pin "1") (pinfunction "1_1") (pintype "passive"))
      (node (ref "U13") (pin "2") (pinfunction "QC_2") (pintype "tri_state"))
      (node (ref "U14") (pin "3") (pinfunction "I3_3") (pintype "input"))
    )
    (net (code "123") (name "Net-(U13A-QD)") (class "Default")
      (node (ref "R14") (pin "1") (pinfunction "1_1") (pintype "passive"))
      (node (ref "U13") (pin "3") (pinfunction "QD_3") (pintype "tri_state"))
      (node (ref "U14") (pin "4") (pinfunction "I4_4") (pintype "input"))
    )
    (net (code "124") (name "Net-(U13A-QE)") (class "Default")
      (node (ref "R15") (pin "1") (pinfunction "1_1") (pintype "passive"))
      (node (ref "U13") (pin "4") (pinfunction "QE_4") (pintype "tri_state"))
      (node (ref "U14") (pin "5") (pinfunction "I5_5") (pintype "input"))
    )
    (net (code "125") (name "Net-(U13A-QF)") (class "Default")
      (node (ref "R16") (pin "1") (pinfunction "1_1") (pintype "passive"))
      (node (ref "U13") (pin "5") (pinfunction "QF_5") (pintype "tri_state"))
      (node (ref "U14") (pin "6") (pinfunction "I6_6") (pintype "input"))
    )
    (net (code "126") (name "Net-(U13A-QG)") (class "Default")
      (node (ref "R17") (pin "1") (pinfunction "1_1") (pintype "passive"))
      (node (ref "U13") (pin "6") (pinfunction "QG_6") (pintype "tri_state"))
      (node (ref "U14") (pin "7") (pinfunction "I7_7") (pintype "input"))
    )
    (net (code "127") (name "Net-(U13A-QH)") (class "Default")
      (node (ref "R18") (pin "1") (pinfunction "1_1") (pintype "passive"))
      (node (ref "U13") (pin "7") (pinfunction "QH_7") (pintype "tri_state"))
      (node (ref "U14") (pin "8") (pinfunction "I8_8") (pintype "input"))
    )
    (net (code "128") (name "OLAT") (class "Default")
      (node (ref "R21") (pin "1") (pinfunction "1_1") (pintype "passive"))
      (node (ref "U$1") (pin "PA8") (pinfunction "PA8_PA8") (pintype "bidirectional"))
      (node (ref "U11") (pin "12") (pinfunction "RCK_12") (pintype "input"))
      (node (ref "U13") (pin "12") (pinfunction "RCK_12") (pintype "input"))
    )
    (net (code "129") (name "SCK") (class "Default")
      (node (ref "JP2") (pin "3") (pinfunction "3_3") (pintype "passive"))
      (node (ref "R19") (pin "1") (pinfunction "1_1") (pintype "passive"))
      (node (ref "U$1") (pin "PB3") (pinfunction "PB3_PB3") (pintype "bidirectional"))
      (node (ref "U11") (pin "11") (pinfunction "SCK_11") (pintype "input"))
      (node (ref "U13") (pin "11") (pinfunction "SCK_11") (pintype "input"))
    )
    (net (code "130") (name "SCK2") (class "Default")
      (node (ref "U$1") (pin "PB10") (pinfunction "PB10_PB10") (pintype "bidirectional"))
      (node (ref "U1") (pin "7") (pinfunction "CLK_7") (pintype "input"))
      (node (ref "U2") (pin "7") (pinfunction "CLK_7") (pintype "input"))
    )
    (net (code "131") (name "SLNK1") (class "Default")
      (node (ref "SJ17") (pin "P$1") (pinfunction "1_P$1") (pintype "passive"))
      (node (ref "U11") (pin "9") (pinfunction "QH*_9") (pintype "tri_state"))
      (node (ref "U13") (pin "14") (pinfunction "SER_14") (pintype "input"))
    )
    (net (code "132") (name "SLNK2") (class "Default")
      (node (ref "SJ16") (pin "P$1") (pinfunction "1_P$1") (pintype "passive"))
      (node (ref "U13") (pin "9") (pinfunction "QH*_9") (pintype "tri_state"))
    )
    (net (code "133") (name "SLNK3") (class "Default")
      (node (ref "SJ19") (pin "P$1") (pinfunction "1_P$1") (pintype "passive"))
      (node (ref "U1") (pin "13") (pinfunction "QH_13") (pintype "output"))
      (node (ref "U2") (pin "1") (pinfunction "SER_1") (pintype "input"))
    )
    (net (code "134") (name "SRV1") (class "Default")
      (node (ref "JP5") (pin "2") (pinfunction "2_2") (pintype "passive"))
      (node (ref "R24") (pin "2") (pinfunction "2_2") (pintype "passive"))
      (node (ref "U$1") (pin "PC9") (pinfunction "PC9_PC9") (pintype "bidirectional"))
    )
    (net (code "135") (name "SRV2") (class "Default")
      (node (ref "JP5") (pin "1") (pinfunction "1_1") (pintype "passive"))
      (node (ref "R25") (pin "2") (pinfunction "2_2") (pintype "passive"))
      (node (ref "U$1") (pin "PC7") (pinfunction "PC7_PC7") (pintype "bidirectional"))
    )
    (net (code "136") (name "SRV3") (class "Default")
      (node (ref "JP6") (pin "2") (pinfunction "2_2") (pintype "passive"))
      (node (ref "R26") (pin "2") (pinfunction "2_2") (pintype "passive"))
      (node (ref "U$1") (pin "PC8") (pinfunction "PC8_PC8") (pintype "bidirectional"))
    )
    (net (code "137") (name "SRV4") (class "Default")
      (node (ref "JP6") (pin "1") (pinfunction "1_1") (pintype "passive"))
      (node (ref "R27") (pin "2") (pinfunction "2_2") (pintype "passive"))
      (node (ref "U$1") (pin "PC6") (pinfunction "PC6_PC6") (pintype "bidirectional"))
    )
    (net (code "138") (name "SRV5") (class "Default")
      (node (ref "JP7") (pin "2") (pinfunction "2_2") (pintype "passive"))
      (node (ref "R64") (pin "2") (pinfunction "2_2") (pintype "passive"))
      (node (ref "U$1") (pin "PF1-PH1") (pinfunction "PF1-PH1_PF1-PH1") (pintype "bidirectional"))
    )
    (net (code "139") (name "SRV6") (class "Default")
      (node (ref "JP7") (pin "1") (pinfunction "1_1") (pintype "passive"))
      (node (ref "R65") (pin "2") (pinfunction "2_2") (pintype "passive"))
      (node (ref "U$1") (pin "PA15") (pinfunction "PA15_PA15") (pintype "bidirectional"))
    )
    (net (code "140") (name "SRV7") (class "Default")
      (node (ref "JP8") (pin "2") (pinfunction "2_2") (pintype "passive"))
      (node (ref "R66") (pin "2") (pinfunction "2_2") (pintype "passive"))
      (node (ref "U$1") (pin "PC12") (pinfunction "PC12_PC12") (pintype "bidirectional"))
    )
    (net (code "141") (name "SRV8") (class "Default")
      (node (ref "JP8") (pin "1") (pinfunction "1_1") (pintype "passive"))
      (node (ref "R67") (pin "2") (pinfunction "2_2") (pintype "passive"))
      (node (ref "U$1") (pin "PD2") (pinfunction "PD2_PD2") (pintype "bidirectional"))
    )
    (net (code "142") (name "TDRV1") (class "Default")
      (node (ref "U$1") (pin "PB12") (pinfunction "PB12_PB12") (pintype "bidirectional"))
      (node (ref "U10") (pin "12") (pinfunction "+IN_12") (pintype "input"))
      (node (ref "U6") (pin "2") (pinfunction "I_2") (pintype "input"))
    )
    (net (code "143") (name "TDRV2") (class "Default")
      (node (ref "U$1") (pin "PB2") (pinfunction "PB2_PB2") (pintype "bidirectional"))
      (node (ref "U10") (pin "3") (pinfunction "+IN_3") (pintype "input"))
      (node (ref "U6") (pin "4") (pinfunction "I_4") (pintype "input"))
    )
    (net (code "144") (name "TDRV3") (class "Default")
      (node (ref "U$1") (pin "PB15") (pinfunction "PB15_PB15") (pintype "bidirectional"))
      (node (ref "U10") (pin "10") (pinfunction "+IN_10") (pintype "input"))
      (node (ref "U5") (pin "4") (pinfunction "I_4") (pintype "input"))
    )
    (net (code "145") (name "TDRV4") (class "Default")
      (node (ref "U$1") (pin "PB1") (pinfunction "PB1_PB1") (pintype "bidirectional"))
      (node (ref "U10") (pin "5") (pinfunction "+IN_5") (pintype "input"))
      (node (ref "U5") (pin "2") (pinfunction "I_2") (pintype "input"))
    )
    (net (code "146") (name "TDRV5") (class "Default")
      (node (ref "U$1") (pin "PA0") (pinfunction "PA0_PA0") (pintype "bidirectional"))
      (node (ref "U4") (pin "2") (pinfunction "I_2") (pintype "input"))
      (node (ref "U9") (pin "12") (pinfunction "+IN_12") (pintype "input"))
    )
    (net (code "147") (name "TDRV6") (class "Default")
      (node (ref "U$1") (pin "PA4") (pinfunction "PA4_PA4") (pintype "bidirectional"))
      (node (ref "U4") (pin "4") (pinfunction "I_4") (pintype "input"))
      (node (ref "U9") (pin "3") (pinfunction "+IN_3") (pintype "input"))
    )
    (net (code "148") (name "TDRV7") (class "Default")
      (node (ref "U$1") (pin "PC3") (pinfunction "PC3_PC3") (pintype "bidirectional"))
      (node (ref "U3") (pin "4") (pinfunction "I_4") (pintype "input"))
      (node (ref "U9") (pin "10") (pinfunction "+IN_10") (pintype "input"))
    )
    (net (code "149") (name "TDRV8") (class "Default")
      (node (ref "U$1") (pin "PC0") (pinfunction "PC0_PC0") (pintype "bidirectional"))
      (node (ref "U3") (pin "2") (pinfunction "I_2") (pintype "input"))
      (node (ref "U9") (pin "5") (pinfunction "+IN_5") (pintype "input"))
    )
    (net (code "150") (name "V+") (class "Default")
      (node (ref "C1") (pin "1") (pinfunction "1_1") (pintype "passive"))
      (node (ref "C2") (pin "+") (pinfunction "+_+") (pintype "passive"))
      (node (ref "L1") (pin "1") (pinfunction "1_1") (pintype "passive"))
      (node (ref "U$1") (pin "E5V") (pinfunction "E5V_E5V") (pintype "power_in"))
      (node (ref "U8") (pin "3") (pinfunction "FB_3") (pintype "bidirectional"))
      (node (ref "U8B") (pin "1") (pinfunction "FB_1") (pintype "input"))
    )
    (net (code "151") (name "unconnected-(H1-MOUNT-PadB3,3)") (class "Default")
      (node (ref "H1") (pin "B3,3") (pinfunction "MOUNT_B3,3") (pintype "passive"))
    )
    (net (code "152") (name "unconnected-(H2-MOUNT-PadB3,3)") (class "Default")
      (node (ref "H2") (pin "B3,3") (pinfunction "MOUNT_B3,3") (pintype "passive"))
    )
    (net (code "153") (name "unconnected-(H3-MOUNT-PadB3,3)") (class "Default")
      (node (ref "H3") (pin "B3,3") (pinfunction "MOUNT_B3,3") (pintype "passive"))
    )
    (net (code "154") (name "unconnected-(H4-MOUNT-PadB3,3)") (class "Default")
      (node (ref "H4") (pin "B3,3") (pinfunction "MOUNT_B3,3") (pintype "passive"))
    )
    (net (code "155") (name "unconnected-(U$1-PadBOOT0)") (class "Default")
      (node (ref "U$1") (pin "BOOT0") (pinfunction "BOOT0_BOOT0") (pintype "bidirectional"))
    )
    (net (code "156") (name "unconnected-(U$1-PadIOREF2)") (class "Default")
      (node (ref "U$1") (pin "IOREF2") (pinfunction "IOREF2_IOREF2") (pintype "input"))
    )
    (net (code "157") (name "unconnected-(U$1-PadNC1-PF7)") (class "Default")
      (node (ref "U$1") (pin "NC1-PF7") (pinfunction "NC1-PF7_NC1-PF7") (pintype "bidirectional"))
    )
    (net (code "158") (name "unconnected-(U$1-PadNC2-PF6)") (class "Default")
      (node (ref "U$1") (pin "NC2-PF6") (pinfunction "NC2-PF6_NC2-PF6") (pintype "bidirectional"))
    )
    (net (code "159") (name "unconnected-(U$1-PadNC3)") (class "Default")
      (node (ref "U$1") (pin "NC3") (pinfunction "NC3_NC3") (pintype "no_connect"))
    )
    (net (code "160") (name "unconnected-(U$1-PadNC4)") (class "Default")
      (node (ref "U$1") (pin "NC4") (pinfunction "NC4_NC4") (pintype "no_connect"))
    )
    (net (code "161") (name "unconnected-(U$1-PadNC5-PD8)") (class "Default")
      (node (ref "U$1") (pin "NC5-PD8") (pinfunction "NC5-PD8_NC5-PD8") (pintype "bidirectional"))
    )
    (net (code "162") (name "unconnected-(U$1-PadNC6-PB11)") (class "Default")
      (node (ref "U$1") (pin "NC6-PB11") (pinfunction "NC6-PB11_NC6-PB11") (pintype "no_connect"))
    )
    (net (code "163") (name "unconnected-(U$1-PadNC7-PF5)") (class "Default")
      (node (ref "U$1") (pin "NC7-PF5") (pinfunction "NC7-PF5_NC7-PF5") (pintype "bidirectional"))
    )
    (net (code "164") (name "unconnected-(U$1-PadNC8-PF4)") (class "Default")
      (node (ref "U$1") (pin "NC8-PF4") (pinfunction "NC8-PF4_NC8-PF4") (pintype "bidirectional"))
    )
    (net (code "165") (name "unconnected-(U$1-PadNRESET)") (class "Default")
      (node (ref "U$1") (pin "NRESET") (pinfunction "NRESET_NRESET") (pintype "input"))
    )
    (net (code "166") (name "unconnected-(U$1-PadPA1)") (class "Default")
      (node (ref "U$1") (pin "PA1") (pinfunction "PA1_PA1") (pintype "bidirectional"))
    )
    (net (code "167") (name "unconnected-(U$1-PadPA2)") (class "Default")
      (node (ref "U$1") (pin "PA2") (pinfunction "PA2_PA2") (pintype "bidirectional"))
    )
    (net (code "168") (name "unconnected-(U$1-PadPA3)") (class "Default")
      (node (ref "U$1") (pin "PA3") (pinfunction "PA3_PA3") (pintype "bidirectional"))
    )
    (net (code "169") (name "unconnected-(U$1-PadPA5)") (class "Default")
      (node (ref "U$1") (pin "PA5") (pinfunction "PA5_PA5") (pintype "bidirectional"))
    )
    (net (code "170") (name "unconnected-(U$1-PadPA7)") (class "Default")
      (node (ref "U$1") (pin "PA7") (pinfunction "PA7_PA7") (pintype "bidirectional"))
    )
    (net (code "171") (name "unconnected-(U$1-PadPA9)") (class "Default")
      (node (ref "U$1") (pin "PA9") (pinfunction "PA9_PA9") (pintype "bidirectional"))
    )
    (net (code "172") (name "unconnected-(U$1-PadPA10)") (class "Default")
      (node (ref "U$1") (pin "PA10") (pinfunction "PA10_PA10") (pintype "bidirectional"))
    )
    (net (code "173") (name "unconnected-(U$1-PadPA11)") (class "Default")
      (node (ref "U$1") (pin "PA11") (pinfunction "PA11_PA11") (pintype "bidirectional"))
    )
    (net (code "174") (name "unconnected-(U$1-PadPA12)") (class "Default")
      (node (ref "U$1") (pin "PA12") (pinfunction "PA12_PA12") (pintype "bidirectional"))
    )
    (net (code "175") (name "unconnected-(U$1-PadPA13)") (class "Default")
      (node (ref "U$1") (pin "PA13") (pinfunction "PA13_PA13") (pintype "bidirectional"))
    )
    (net (code "176") (name "unconnected-(U$1-PadPA14)") (class "Default")
      (node (ref "U$1") (pin "PA14") (pinfunction "PA14_PA14") (pintype "bidirectional"))
    )
    (net (code "177") (name "unconnected-(U$1-PadPB0)") (class "Default")
      (node (ref "U$1") (pin "PB0") (pinfunction "PB0_PB0") (pintype "bidirectional"))
    )
    (net (code "178") (name "unconnected-(U$1-PadPB13)") (class "Default")
      (node (ref "U$1") (pin "PB13") (pinfunction "PB13_PB13") (pintype "bidirectional"))
    )
    (net (code "179") (name "unconnected-(U$1-PadPC1)") (class "Default")
      (node (ref "U$1") (pin "PC1") (pinfunction "PC1_PC1") (pintype "bidirectional"))
    )
    (net (code "180") (name "unconnected-(U$1-PadPC4)") (class "Default")
      (node (ref "U$1") (pin "PC4") (pinfunction "PC4_PC4") (pintype "bidirectional"))
    )
    (net (code "181") (name "unconnected-(U$1-PadPC5)") (class "Default")
      (node (ref "U$1") (pin "PC5") (pinfunction "PC5_PC5") (pintype "bidirectional"))
    )
    (net (code "182") (name "unconnected-(U$1-PadPC13)") (class "Default")
      (node (ref "U$1") (pin "PC13") (pinfunction "PC13_PC13") (pintype "bidirectional"))
    )
    (net (code "183") (name "unconnected-(U$1-PadPC14)") (class "Default")
      (node (ref "U$1") (pin "PC14") (pinfunction "PC14_PC14") (pintype "bidirectional"))
    )
    (net (code "184") (name "unconnected-(U$1-PadPC15)") (class "Default")
      (node (ref "U$1") (pin "PC15") (pinfunction "PC15_PC15") (pintype "bidirectional"))
    )
    (net (code "185") (name "unconnected-(U$1-PadPF0-PH0)") (class "Default")
      (node (ref "U$1") (pin "PF0-PH0") (pinfunction "PF0-PH0_PF0-PH0") (pintype "bidirectional"))
    )
  )
)
